# rs41.net
KiCad netlist of a schematic drawn in EAGLE
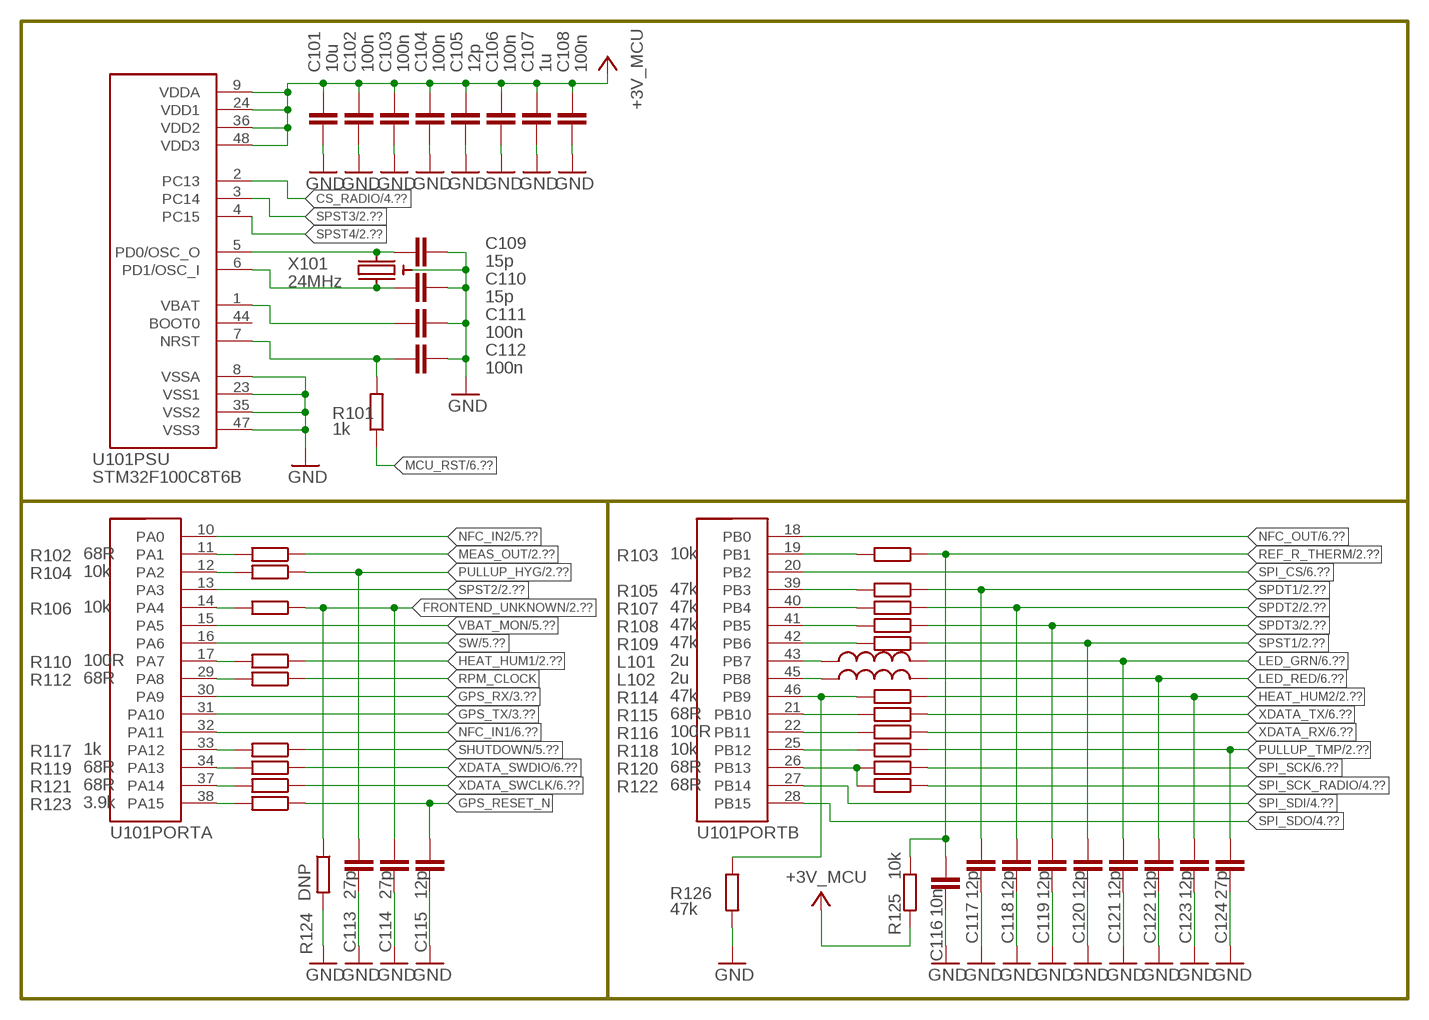
[diagram p0: schematic, sheet 1]
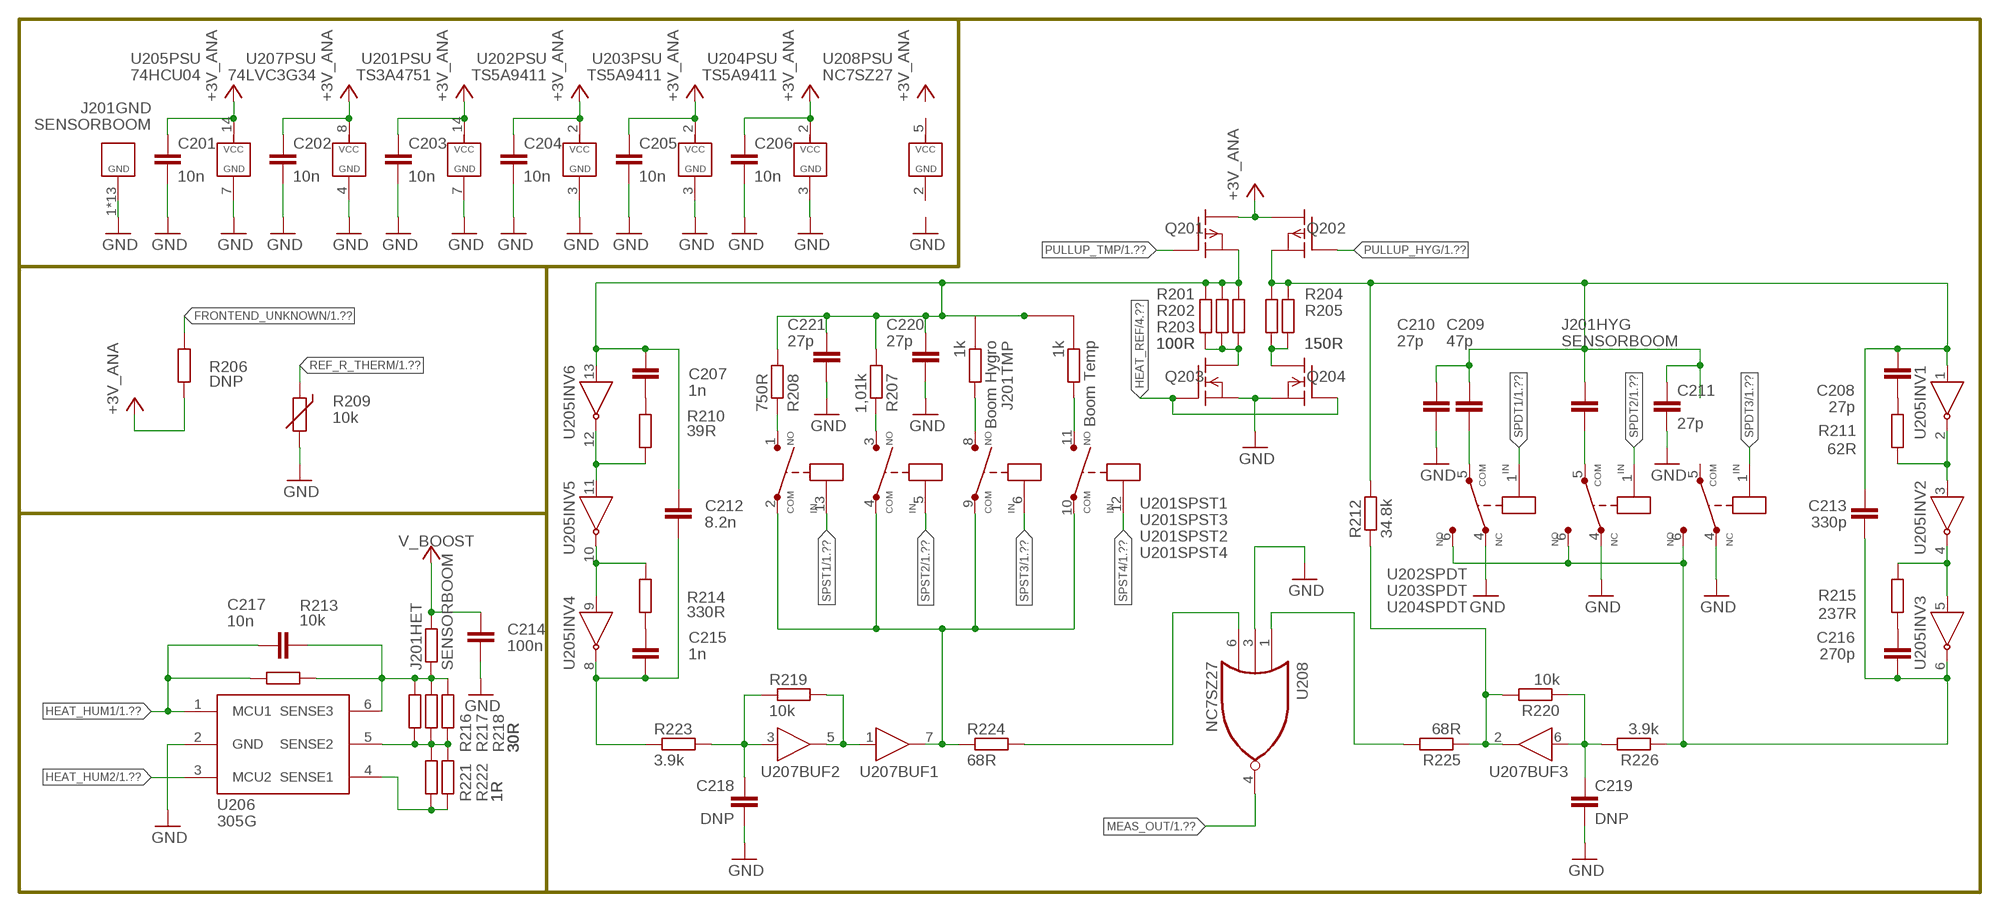
[diagram p1: schematic, sheet 2]
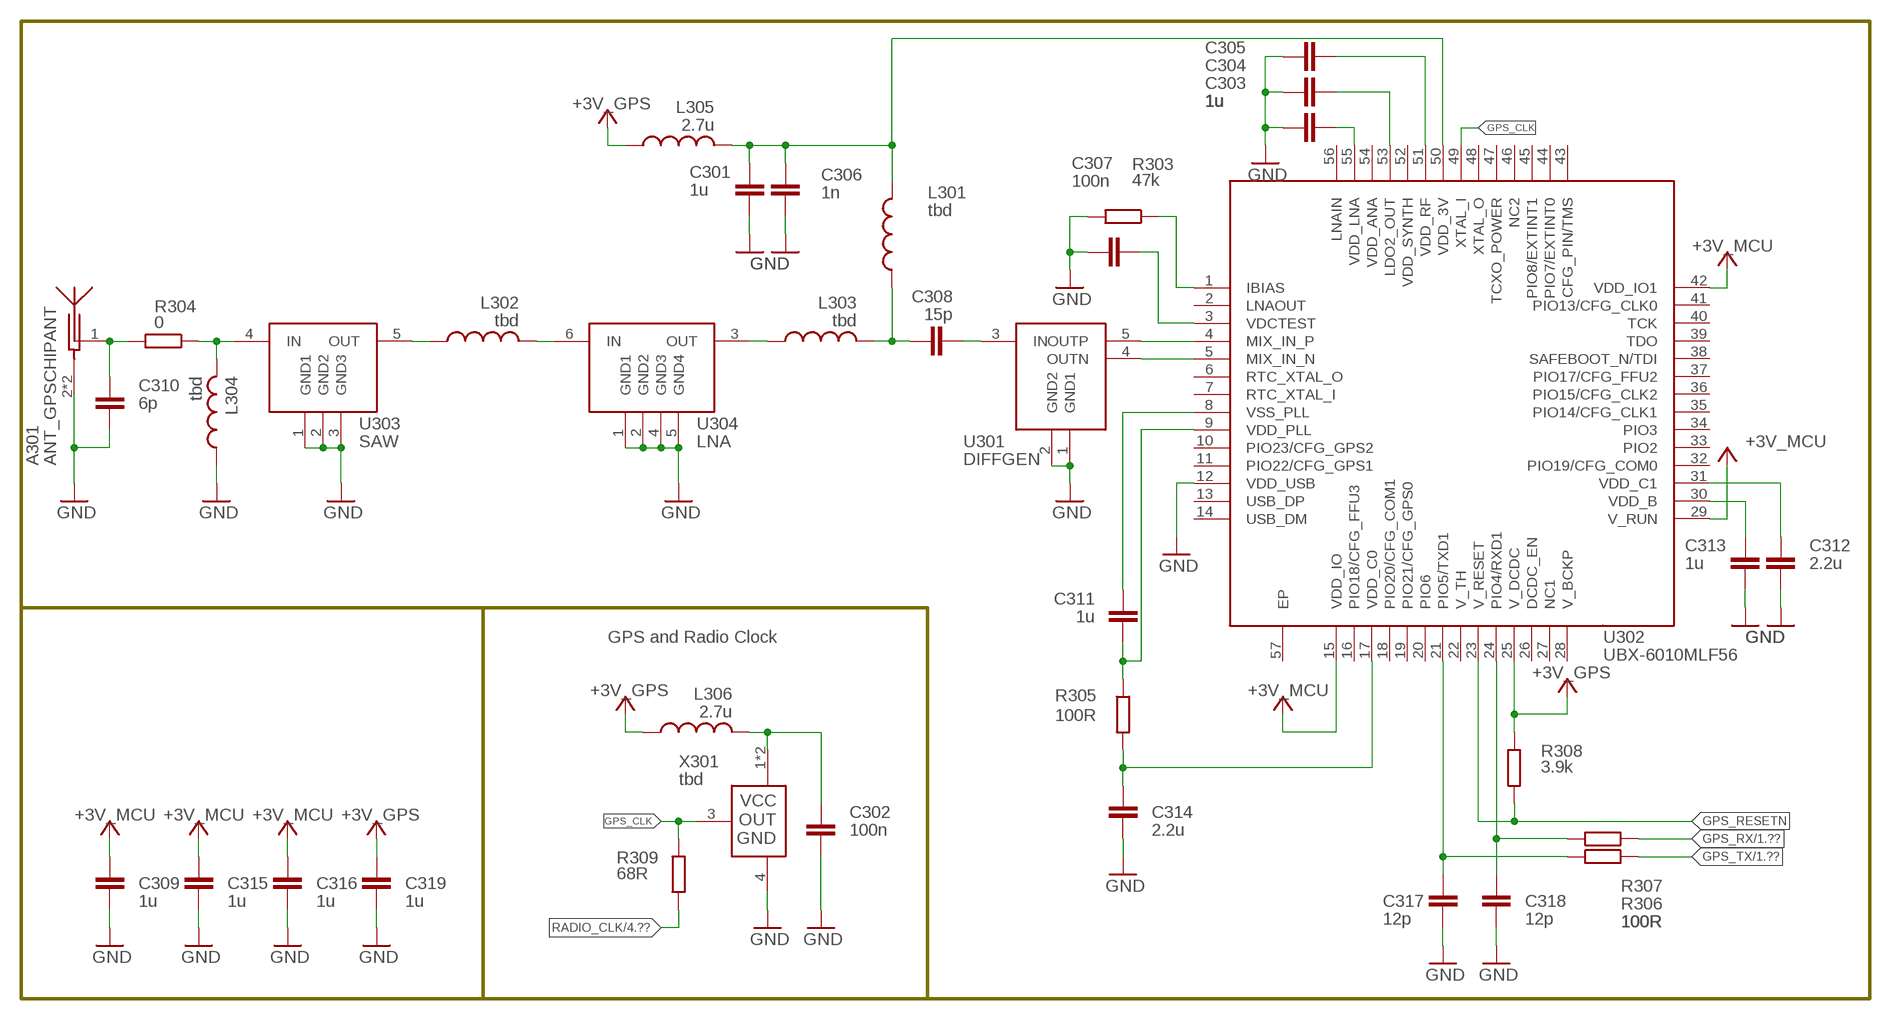
[diagram p2: schematic, sheet 3]
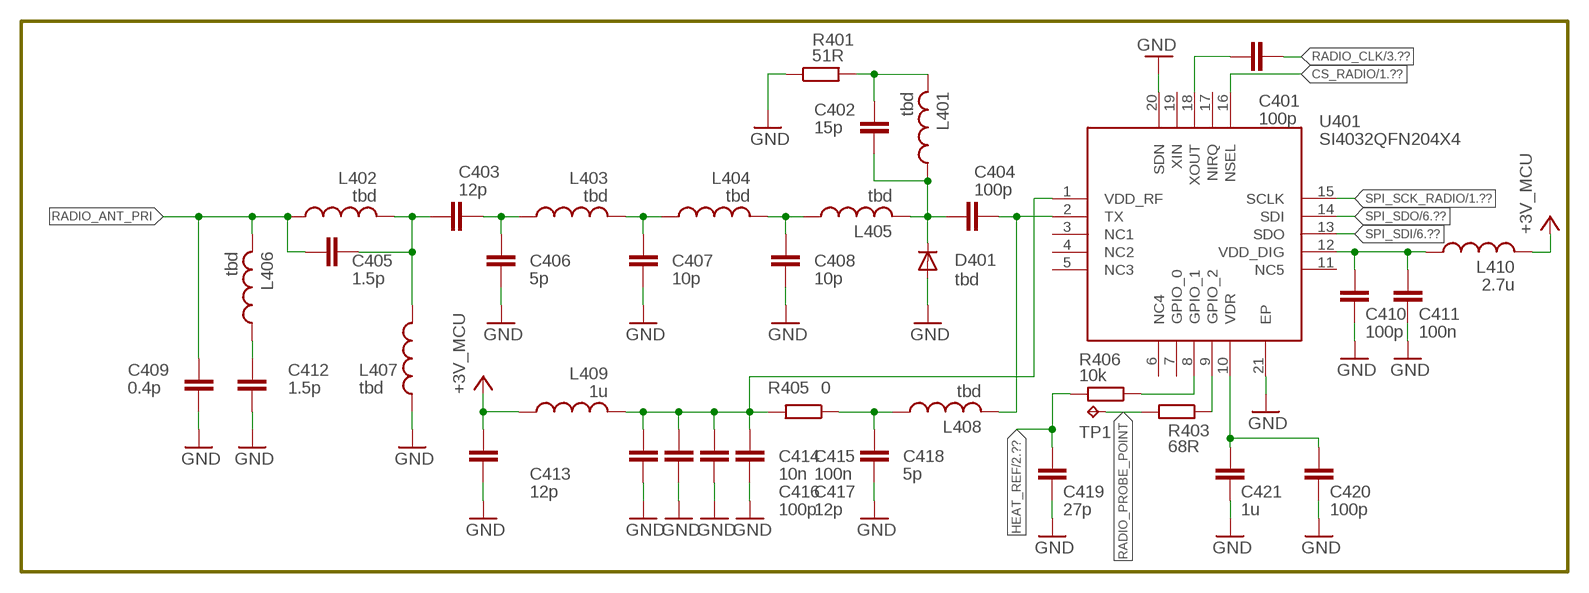
[diagram p3: schematic, sheet 4]
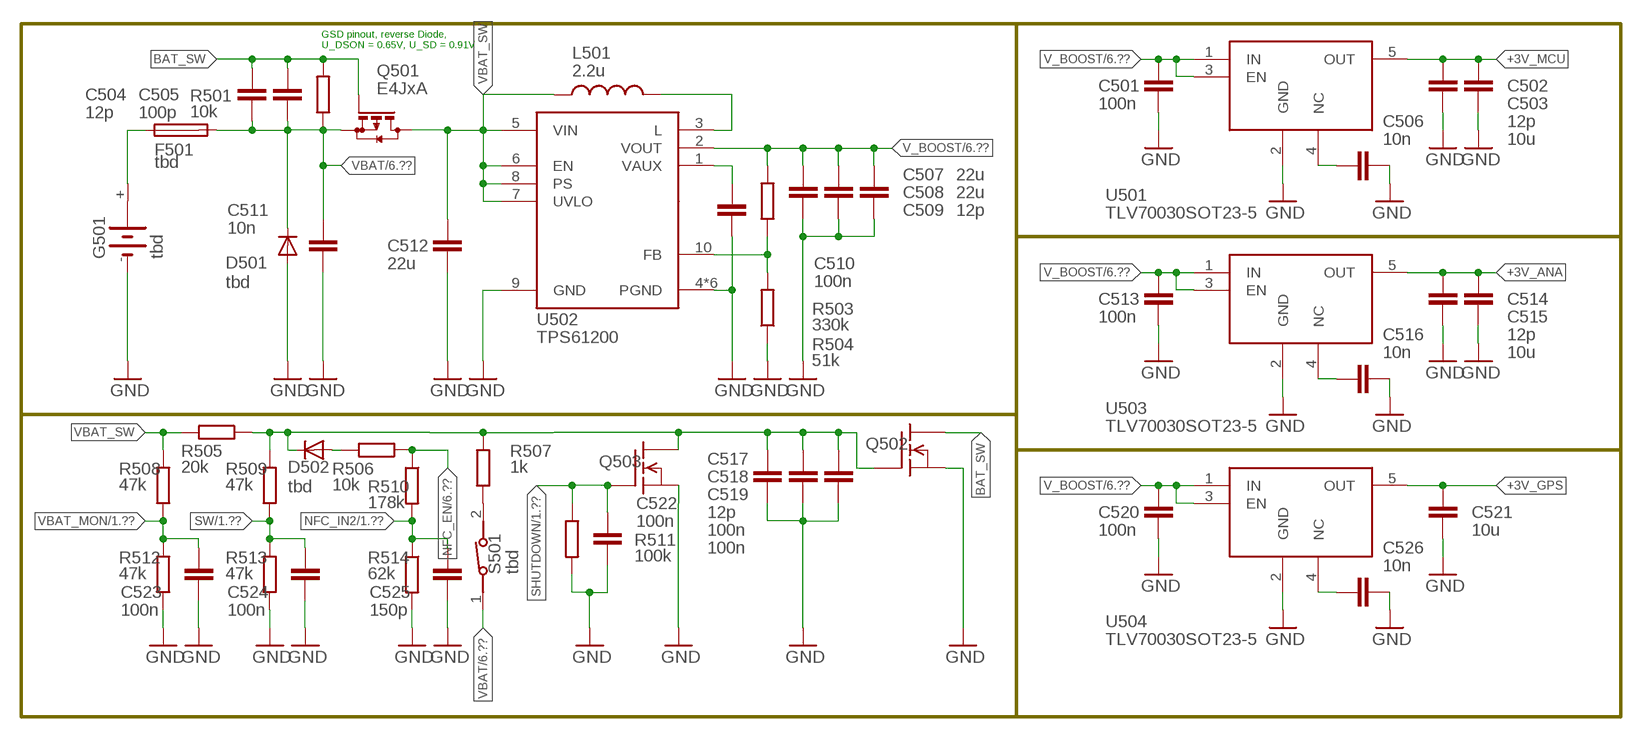
[diagram p4: schematic, sheet 5]
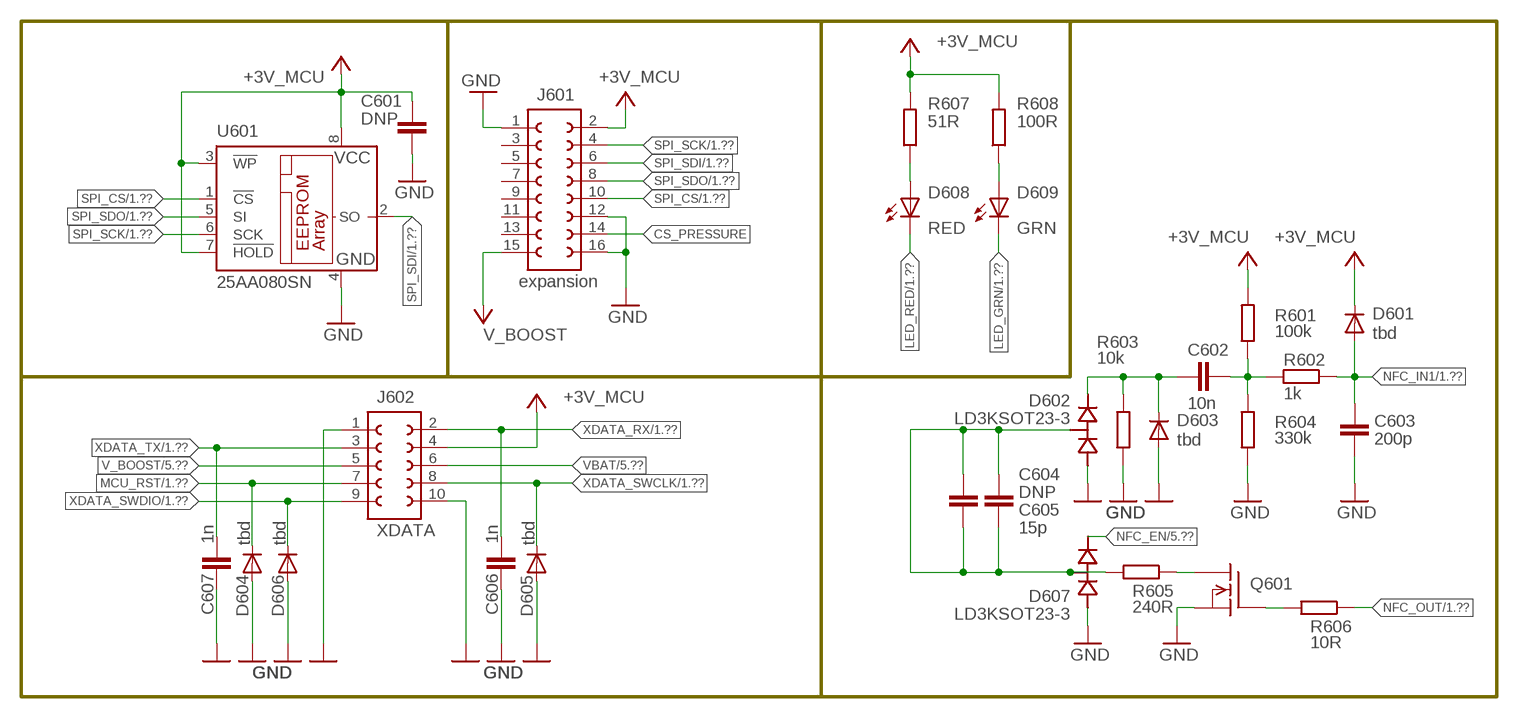
[diagram p5: schematic, sheet 6]

(export (version "E")
  (design (tool "Eeschema 10.0.6"))
  (components
    (comp (ref "C401")
      (value "100p")
      (footprint "eagle-import:C0402")
      (libsource (lib "eagle-import") (part "C-EUC0402"))
    )
    (comp (ref "C402")
      (value "15p")
      (footprint "eagle-import:C0402")
      (libsource (lib "eagle-import") (part "C-EUC0402"))
    )
    (comp (ref "C403")
      (value "12p")
      (footprint "eagle-import:C0402")
      (libsource (lib "eagle-import") (part "C-EUC0402"))
    )
    (comp (ref "C404")
      (value "100p")
      (footprint "eagle-import:C0402")
      (libsource (lib "eagle-import") (part "C-EUC0402"))
    )
    (comp (ref "C405")
      (value "1.5p")
      (footprint "eagle-import:C0402")
      (libsource (lib "eagle-import") (part "C-EUC0402"))
    )
    (comp (ref "C406")
      (value "5p")
      (footprint "eagle-import:C0402")
      (libsource (lib "eagle-import") (part "C-EUC0402"))
    )
    (comp (ref "C407")
      (value "10p")
      (footprint "eagle-import:C0402")
      (libsource (lib "eagle-import") (part "C-EUC0402"))
    )
    (comp (ref "C408")
      (value "10p")
      (footprint "eagle-import:C0402")
      (libsource (lib "eagle-import") (part "C-EUC0402"))
    )
    (comp (ref "C409")
      (value "0.4p")
      (footprint "eagle-import:C0402")
      (libsource (lib "eagle-import") (part "C-EUC0402"))
    )
    (comp (ref "C410")
      (value "100p")
      (footprint "eagle-import:C0402")
      (libsource (lib "eagle-import") (part "C-EUC0402"))
    )
    (comp (ref "C411")
      (value "100n")
      (footprint "eagle-import:C0402")
      (libsource (lib "eagle-import") (part "C-EUC0402"))
    )
    (comp (ref "C412")
      (value "1.5p")
      (footprint "eagle-import:C0402")
      (libsource (lib "eagle-import") (part "C-EUC0402"))
    )
    (comp (ref "C413")
      (value "12p")
      (footprint "eagle-import:C0402")
      (libsource (lib "eagle-import") (part "C-EUC0402"))
    )
    (comp (ref "C414")
      (value "10n")
      (footprint "eagle-import:C0603")
      (libsource (lib "eagle-import") (part "C-EUC0603"))
    )
    (comp (ref "C415")
      (value "100n")
      (footprint "eagle-import:C0402")
      (libsource (lib "eagle-import") (part "C-EUC0402"))
    )
    (comp (ref "C416")
      (value "100p")
      (footprint "eagle-import:C0402")
      (libsource (lib "eagle-import") (part "C-EUC0402"))
    )
    (comp (ref "C417")
      (value "12p")
      (footprint "eagle-import:C0402")
      (libsource (lib "eagle-import") (part "C-EUC0402"))
    )
    (comp (ref "C418")
      (value "5p")
      (footprint "eagle-import:C0402")
      (libsource (lib "eagle-import") (part "C-EUC0402"))
    )
    (comp (ref "C419")
      (value "27p")
      (footprint "eagle-import:C0402")
      (libsource (lib "eagle-import") (part "C-EUC0402"))
    )
    (comp (ref "C420")
      (value "100p")
      (footprint "eagle-import:C0402")
      (libsource (lib "eagle-import") (part "C-EUC0402"))
    )
    (comp (ref "C421")
      (value "1u")
      (footprint "eagle-import:C0402")
      (libsource (lib "eagle-import") (part "C-EUC0402"))
    )
    (comp (ref "D401")
      (value "tbd")
      (footprint "eagle-import:DO41-10")
      (libsource (lib "eagle-import") (part "1N4004"))
    )
    (comp (ref "L401")
      (value "tbd")
      (footprint "eagle-import:0402")
      (libsource (lib "eagle-import") (part "L0402"))
    )
    (comp (ref "L402")
      (value "tbd")
      (footprint "eagle-import:0402")
      (libsource (lib "eagle-import") (part "L0402"))
    )
    (comp (ref "L403")
      (value "tbd")
      (footprint "eagle-import:0402")
      (libsource (lib "eagle-import") (part "L0402"))
    )
    (comp (ref "L404")
      (value "tbd")
      (footprint "eagle-import:0402")
      (libsource (lib "eagle-import") (part "L0402"))
    )
    (comp (ref "L405")
      (value "tbd")
      (footprint "eagle-import:0402")
      (libsource (lib "eagle-import") (part "L0402"))
    )
    (comp (ref "L406")
      (value "tbd")
      (footprint "eagle-import:0402")
      (libsource (lib "eagle-import") (part "L0402"))
    )
    (comp (ref "L407")
      (value "tbd")
      (footprint "eagle-import:0402")
      (libsource (lib "eagle-import") (part "L0402"))
    )
    (comp (ref "L408")
      (value "tbd")
      (footprint "eagle-import:0402")
      (libsource (lib "eagle-import") (part "L0402"))
    )
    (comp (ref "L409")
      (value "1u")
      (footprint "eagle-import:0402")
      (libsource (lib "eagle-import") (part "L0402"))
    )
    (comp (ref "L410")
      (value "2.7u")
      (footprint "eagle-import:0402")
      (libsource (lib "eagle-import") (part "L0402"))
    )
    (comp (ref "R401")
      (value "51R")
      (footprint "eagle-import:R0402")
      (libsource (lib "eagle-import") (part "R-EU_R0402"))
    )
    (comp (ref "R403")
      (value "68R")
      (footprint "eagle-import:R0402")
      (libsource (lib "eagle-import") (part "R-EU_R0402"))
    )
    (comp (ref "R405")
      (value "0")
      (footprint "eagle-import:R0402")
      (libsource (lib "eagle-import") (part "R-EU_R0402"))
    )
    (comp (ref "R406")
      (value "10k")
      (footprint "eagle-import:R0402")
      (libsource (lib "eagle-import") (part "R-EU_R0402"))
    )
    (comp (ref "TP1")
      (value "TPPAD1-13")
      (footprint "eagle-import:P1-13")
      (libsource (lib "eagle-import") (part "TPPAD1-13"))
    )
    (comp (ref "U401")
      (value "SI4032QFN204X4")
      (footprint "eagle-import:QFN20_0.5MM")
      (libsource (lib "eagle-import") (part "SI4032QFN204X4"))
    )
    (comp (ref "C101")
      (value "10u")
      (footprint "eagle-import:C0603")
      (libsource (lib "eagle-import") (part "C-EUC0603"))
    )
    (comp (ref "C102")
      (value "100n")
      (footprint "eagle-import:C0402")
      (libsource (lib "eagle-import") (part "C-EUC0402"))
    )
    (comp (ref "C103")
      (value "100n")
      (footprint "eagle-import:C0402")
      (libsource (lib "eagle-import") (part "C-EUC0402"))
    )
    (comp (ref "C104")
      (value "100n")
      (footprint "eagle-import:C0402")
      (libsource (lib "eagle-import") (part "C-EUC0402"))
    )
    (comp (ref "C105")
      (value "12p")
      (footprint "eagle-import:C0402")
      (libsource (lib "eagle-import") (part "C-EUC0402"))
    )
    (comp (ref "C106")
      (value "100n")
      (footprint "eagle-import:C0402")
      (libsource (lib "eagle-import") (part "C-EUC0402"))
    )
    (comp (ref "C107")
      (value "1u")
      (footprint "eagle-import:C0402")
      (libsource (lib "eagle-import") (part "C-EUC0402"))
    )
    (comp (ref "C108")
      (value "100n")
      (footprint "eagle-import:C0402")
      (libsource (lib "eagle-import") (part "C-EUC0402"))
    )
    (comp (ref "C109")
      (value "15p")
      (footprint "eagle-import:C0402")
      (libsource (lib "eagle-import") (part "C-EUC0402"))
    )
    (comp (ref "C110")
      (value "15p")
      (footprint "eagle-import:C0402")
      (libsource (lib "eagle-import") (part "C-EUC0402"))
    )
    (comp (ref "C111")
      (value "100n")
      (footprint "eagle-import:C0402")
      (libsource (lib "eagle-import") (part "C-EUC0402"))
    )
    (comp (ref "C112")
      (value "100n")
      (footprint "eagle-import:C0402")
      (libsource (lib "eagle-import") (part "C-EUC0402"))
    )
    (comp (ref "C113")
      (value "27p")
      (footprint "eagle-import:C0402")
      (libsource (lib "eagle-import") (part "C-EUC0402"))
    )
    (comp (ref "C114")
      (value "27p")
      (footprint "eagle-import:C0402")
      (libsource (lib "eagle-import") (part "C-EUC0402"))
    )
    (comp (ref "C115")
      (value "12p")
      (footprint "eagle-import:C0402")
      (libsource (lib "eagle-import") (part "C-EUC0402"))
    )
    (comp (ref "C116")
      (value "10n")
      (footprint "eagle-import:C0402")
      (libsource (lib "eagle-import") (part "C-EUC0402"))
    )
    (comp (ref "C117")
      (value "12p")
      (footprint "eagle-import:C0402")
      (libsource (lib "eagle-import") (part "C-EUC0402"))
    )
    (comp (ref "C118")
      (value "12p")
      (footprint "eagle-import:C0402")
      (libsource (lib "eagle-import") (part "C-EUC0402"))
    )
    (comp (ref "C119")
      (value "12p")
      (footprint "eagle-import:C0402")
      (libsource (lib "eagle-import") (part "C-EUC0402"))
    )
    (comp (ref "C120")
      (value "12p")
      (footprint "eagle-import:C0402")
      (libsource (lib "eagle-import") (part "C-EUC0402"))
    )
    (comp (ref "C121")
      (value "12p")
      (footprint "eagle-import:C0402")
      (libsource (lib "eagle-import") (part "C-EUC0402"))
    )
    (comp (ref "C122")
      (value "12p")
      (footprint "eagle-import:C0402")
      (libsource (lib "eagle-import") (part "C-EUC0402"))
    )
    (comp (ref "C123")
      (value "12p")
      (footprint "eagle-import:C0402")
      (libsource (lib "eagle-import") (part "C-EUC0402"))
    )
    (comp (ref "C124")
      (value "27p")
      (footprint "eagle-import:C0402")
      (libsource (lib "eagle-import") (part "C-EUC0402"))
    )
    (comp (ref "L101")
      (value "2u")
      (footprint "eagle-import:0402")
      (libsource (lib "eagle-import") (part "L0402"))
    )
    (comp (ref "L102")
      (value "2u")
      (footprint "eagle-import:0402")
      (libsource (lib "eagle-import") (part "L0402"))
    )
    (comp (ref "R101")
      (value "1k")
      (footprint "eagle-import:R0402")
      (libsource (lib "eagle-import") (part "R-EU_R0402"))
    )
    (comp (ref "R102")
      (value "68R")
      (footprint "eagle-import:R0402")
      (libsource (lib "eagle-import") (part "R-EU_R0402"))
    )
    (comp (ref "R103")
      (value "10k")
      (footprint "eagle-import:R0402")
      (libsource (lib "eagle-import") (part "R-EU_R0402"))
    )
    (comp (ref "R104")
      (value "10k")
      (footprint "eagle-import:R0402")
      (libsource (lib "eagle-import") (part "R-EU_R0402"))
    )
    (comp (ref "R105")
      (value "47k")
      (footprint "eagle-import:R0402")
      (libsource (lib "eagle-import") (part "R-EU_R0402"))
    )
    (comp (ref "R106")
      (value "10k")
      (footprint "eagle-import:R0402")
      (libsource (lib "eagle-import") (part "R-EU_R0402"))
    )
    (comp (ref "R107")
      (value "47k")
      (footprint "eagle-import:R0402")
      (libsource (lib "eagle-import") (part "R-EU_R0402"))
    )
    (comp (ref "R108")
      (value "47k")
      (footprint "eagle-import:R0402")
      (libsource (lib "eagle-import") (part "R-EU_R0402"))
    )
    (comp (ref "R109")
      (value "47k")
      (footprint "eagle-import:R0402")
      (libsource (lib "eagle-import") (part "R-EU_R0402"))
    )
    (comp (ref "R110")
      (value "100R")
      (footprint "eagle-import:R0402")
      (libsource (lib "eagle-import") (part "R-EU_R0402"))
    )
    (comp (ref "R112")
      (value "68R")
      (footprint "eagle-import:R0402")
      (libsource (lib "eagle-import") (part "R-EU_R0402"))
    )
    (comp (ref "R114")
      (value "47k")
      (footprint "eagle-import:R0402")
      (libsource (lib "eagle-import") (part "R-EU_R0402"))
    )
    (comp (ref "R115")
      (value "68R")
      (footprint "eagle-import:R0402")
      (libsource (lib "eagle-import") (part "R-EU_R0402"))
    )
    (comp (ref "R116")
      (value "100R")
      (footprint "eagle-import:R0402")
      (libsource (lib "eagle-import") (part "R-EU_R0402"))
    )
    (comp (ref "R117")
      (value "1k")
      (footprint "eagle-import:R0402")
      (libsource (lib "eagle-import") (part "R-EU_R0402"))
    )
    (comp (ref "R118")
      (value "10k")
      (footprint "eagle-import:R0402")
      (libsource (lib "eagle-import") (part "R-EU_R0402"))
    )
    (comp (ref "R119")
      (value "68R")
      (footprint "eagle-import:R0402")
      (libsource (lib "eagle-import") (part "R-EU_R0402"))
    )
    (comp (ref "R120")
      (value "68R")
      (footprint "eagle-import:R0402")
      (libsource (lib "eagle-import") (part "R-EU_R0402"))
    )
    (comp (ref "R121")
      (value "68R")
      (footprint "eagle-import:R0402")
      (libsource (lib "eagle-import") (part "R-EU_R0402"))
    )
    (comp (ref "R122")
      (value "68R")
      (footprint "eagle-import:R0402")
      (libsource (lib "eagle-import") (part "R-EU_R0402"))
    )
    (comp (ref "R123")
      (value "3.9k")
      (footprint "eagle-import:R0402")
      (libsource (lib "eagle-import") (part "R-EU_R0402"))
    )
    (comp (ref "R124")
      (value "DNP")
      (footprint "eagle-import:R0402")
      (libsource (lib "eagle-import") (part "R-EU_R0402"))
    )
    (comp (ref "R125")
      (value "10k")
      (footprint "eagle-import:R0402")
      (libsource (lib "eagle-import") (part "R-EU_R0402"))
    )
    (comp (ref "R126")
      (value "47k")
      (footprint "eagle-import:R0402")
      (libsource (lib "eagle-import") (part "R-EU_R0402"))
    )
    (comp (ref "U101")
      (value "STM32F100C8T6B")
      (footprint "eagle-import:LQFP48")
      (libsource (lib "eagle-import") (part "STM32F100C8LQFP48"))
    )
    (comp (ref "X101")
      (value "24MHz")
      (footprint "eagle-import:OSCCC650X400X120")
      (libsource (lib "eagle-import") (part "OSC_MCU"))
    )
    (comp (ref "A301")
      (value "ANT_GPSCHIPANT")
      (footprint "eagle-import:DFN100X60X40-3")
      (libsource (lib "eagle-import") (part "ANT_GPSCHIPANT"))
    )
    (comp (ref "C301")
      (value "1u")
      (footprint "eagle-import:C0402")
      (libsource (lib "eagle-import") (part "C-EUC0402"))
    )
    (comp (ref "C302")
      (value "100n")
      (footprint "eagle-import:C0402")
      (libsource (lib "eagle-import") (part "C-EUC0402"))
    )
    (comp (ref "C303")
      (value "1u")
      (footprint "eagle-import:C0402")
      (libsource (lib "eagle-import") (part "C-EUC0402"))
    )
    (comp (ref "C304")
      (value "1u")
      (footprint "eagle-import:C0402")
      (libsource (lib "eagle-import") (part "C-EUC0402"))
    )
    (comp (ref "C305")
      (value "1u")
      (footprint "eagle-import:C0402")
      (libsource (lib "eagle-import") (part "C-EUC0402"))
    )
    (comp (ref "C306")
      (value "1n")
      (footprint "eagle-import:C0402")
      (libsource (lib "eagle-import") (part "C-EUC0402"))
    )
    (comp (ref "C307")
      (value "100n")
      (footprint "eagle-import:C0402")
      (libsource (lib "eagle-import") (part "C-EUC0402"))
    )
    (comp (ref "C308")
      (value "15p")
      (footprint "eagle-import:C0402")
      (libsource (lib "eagle-import") (part "C-EUC0402"))
    )
    (comp (ref "C309")
      (value "1u")
      (footprint "eagle-import:C0402")
      (libsource (lib "eagle-import") (part "C-EUC0402"))
    )
    (comp (ref "C310")
      (value "6p")
      (footprint "eagle-import:C0402")
      (libsource (lib "eagle-import") (part "C-EUC0402"))
    )
    (comp (ref "C311")
      (value "1u")
      (footprint "eagle-import:C0402")
      (libsource (lib "eagle-import") (part "C-EUC0402"))
    )
    (comp (ref "C312")
      (value "2.2u")
      (footprint "eagle-import:C0603")
      (libsource (lib "eagle-import") (part "C-EUC0603"))
    )
    (comp (ref "C313")
      (value "1u")
      (footprint "eagle-import:C0402")
      (libsource (lib "eagle-import") (part "C-EUC0402"))
    )
    (comp (ref "C314")
      (value "2.2u")
      (footprint "eagle-import:C0603")
      (libsource (lib "eagle-import") (part "C-EUC0603"))
    )
    (comp (ref "C315")
      (value "1u")
      (footprint "eagle-import:C0402")
      (libsource (lib "eagle-import") (part "C-EUC0402"))
    )
    (comp (ref "C316")
      (value "1u")
      (footprint "eagle-import:C0402")
      (libsource (lib "eagle-import") (part "C-EUC0402"))
    )
    (comp (ref "C317")
      (value "12p")
      (footprint "eagle-import:C0402")
      (libsource (lib "eagle-import") (part "C-EUC0402"))
    )
    (comp (ref "C318")
      (value "12p")
      (footprint "eagle-import:C0402")
      (libsource (lib "eagle-import") (part "C-EUC0402"))
    )
    (comp (ref "C319")
      (value "1u")
      (footprint "eagle-import:C0402")
      (libsource (lib "eagle-import") (part "C-EUC0402"))
    )
    (comp (ref "L301")
      (value "tbd")
      (footprint "eagle-import:0402")
      (libsource (lib "eagle-import") (part "L0402"))
    )
    (comp (ref "L302")
      (value "tbd")
      (footprint "eagle-import:0402")
      (libsource (lib "eagle-import") (part "L0402"))
    )
    (comp (ref "L303")
      (value "tbd")
      (footprint "eagle-import:0402")
      (libsource (lib "eagle-import") (part "L0402"))
    )
    (comp (ref "L304")
      (value "tbd")
      (footprint "eagle-import:0402")
      (libsource (lib "eagle-import") (part "L0402"))
    )
    (comp (ref "L305")
      (value "2.7u")
      (footprint "eagle-import:0402")
      (libsource (lib "eagle-import") (part "L0402"))
    )
    (comp (ref "L306")
      (value "2.7u")
      (footprint "eagle-import:0402")
      (libsource (lib "eagle-import") (part "L0402"))
    )
    (comp (ref "R303")
      (value "47k")
      (footprint "eagle-import:R0402")
      (libsource (lib "eagle-import") (part "R-EU_R0402"))
    )
    (comp (ref "R304")
      (value "0")
      (footprint "eagle-import:R0402")
      (libsource (lib "eagle-import") (part "R-EU_R0402"))
    )
    (comp (ref "R305")
      (value "100R")
      (footprint "eagle-import:R0402")
      (libsource (lib "eagle-import") (part "R-EU_R0402"))
    )
    (comp (ref "R306")
      (value "100R")
      (footprint "eagle-import:R0402")
      (libsource (lib "eagle-import") (part "R-EU_R0402"))
    )
    (comp (ref "R307")
      (value "100R")
      (footprint "eagle-import:R0402")
      (libsource (lib "eagle-import") (part "R-EU_R0402"))
    )
    (comp (ref "R308")
      (value "3.9k")
      (footprint "eagle-import:R0402")
      (libsource (lib "eagle-import") (part "R-EU_R0402"))
    )
    (comp (ref "R309")
      (value "68R")
      (footprint "eagle-import:R0402")
      (libsource (lib "eagle-import") (part "R-EU_R0402"))
    )
    (comp (ref "U301")
      (value "DIFFGEN")
      (footprint "eagle-import:SOT23-5")
      (libsource (lib "eagle-import") (part "DIFFGEN"))
    )
    (comp (ref "U302")
      (value "UBX-6010MLF56")
      (footprint "eagle-import:QFN56_0.5MM")
      (libsource (lib "eagle-import") (part "UBX-6010MLF56"))
    )
    (comp (ref "U303")
      (value "SAW")
      (footprint "eagle-import:SOT23-5")
      (libsource (lib "eagle-import") (part "SAW"))
    )
    (comp (ref "U304")
      (value "LNA")
      (footprint "eagle-import:SOT23-6")
      (libsource (lib "eagle-import") (part "LNA"))
    )
    (comp (ref "X301")
      (value "tbd")
      (footprint "eagle-import:OSCCC650X400X120")
      (libsource (lib "eagle-import") (part "OSC_GPSXTAL4"))
    )
    (comp (ref "C201")
      (value "10n")
      (footprint "eagle-import:C0402")
      (libsource (lib "eagle-import") (part "C-EUC0402"))
    )
    (comp (ref "C202")
      (value "10n")
      (footprint "eagle-import:C0402")
      (libsource (lib "eagle-import") (part "C-EUC0402"))
    )
    (comp (ref "C203")
      (value "10n")
      (footprint "eagle-import:C0402")
      (libsource (lib "eagle-import") (part "C-EUC0402"))
    )
    (comp (ref "C204")
      (value "10n")
      (footprint "eagle-import:C0402")
      (libsource (lib "eagle-import") (part "C-EUC0402"))
    )
    (comp (ref "C205")
      (value "10n")
      (footprint "eagle-import:C0402")
      (libsource (lib "eagle-import") (part "C-EUC0402"))
    )
    (comp (ref "C206")
      (value "10n")
      (footprint "eagle-import:C0402")
      (libsource (lib "eagle-import") (part "C-EUC0402"))
    )
    (comp (ref "C207")
      (value "1n")
      (footprint "eagle-import:C0402")
      (libsource (lib "eagle-import") (part "C-EUC0402"))
    )
    (comp (ref "C208")
      (value "27p")
      (footprint "eagle-import:C0402")
      (libsource (lib "eagle-import") (part "C-EUC0402"))
    )
    (comp (ref "C209")
      (value "47p")
      (footprint "eagle-import:C0603")
      (libsource (lib "eagle-import") (part "C-EUC0603"))
    )
    (comp (ref "C210")
      (value "27p")
      (footprint "eagle-import:C0402")
      (libsource (lib "eagle-import") (part "C-EUC0402"))
    )
    (comp (ref "C211")
      (value "27p")
      (footprint "eagle-import:C0402")
      (libsource (lib "eagle-import") (part "C-EUC0402"))
    )
    (comp (ref "C212")
      (value "8.2n")
      (footprint "eagle-import:C0603")
      (libsource (lib "eagle-import") (part "C-EUC0603"))
    )
    (comp (ref "C213")
      (value "330p")
      (footprint "eagle-import:C0402")
      (libsource (lib "eagle-import") (part "C-EUC0402"))
    )
    (comp (ref "C214")
      (value "100n")
      (footprint "eagle-import:C0402")
      (libsource (lib "eagle-import") (part "C-EUC0402"))
    )
    (comp (ref "C215")
      (value "1n")
      (footprint "eagle-import:C0402")
      (libsource (lib "eagle-import") (part "C-EUC0402"))
    )
    (comp (ref "C216")
      (value "270p")
      (footprint "eagle-import:C0402")
      (libsource (lib "eagle-import") (part "C-EUC0402"))
    )
    (comp (ref "C217")
      (value "10n")
      (footprint "eagle-import:C0402")
      (libsource (lib "eagle-import") (part "C-EUC0402"))
    )
    (comp (ref "C218")
      (value "DNP")
      (footprint "eagle-import:C0402")
      (libsource (lib "eagle-import") (part "C-EUC0402"))
    )
    (comp (ref "C219")
      (value "DNP")
      (footprint "eagle-import:C0402")
      (libsource (lib "eagle-import") (part "C-EUC0402"))
    )
    (comp (ref "C220")
      (value "27p")
      (footprint "eagle-import:C0402")
      (libsource (lib "eagle-import") (part "C-EUC0402"))
    )
    (comp (ref "C221")
      (value "27p")
      (footprint "eagle-import:C0402")
      (libsource (lib "eagle-import") (part "C-EUC0402"))
    )
    (comp (ref "J201")
      (value "SENSORBOOM")
      (footprint "eagle-import:687316124422")
      (libsource (lib "eagle-import") (part "SENSORBOOM"))
    )
    (comp (ref "Q201")
      (value "BSS92")
      (footprint "eagle-import:TO92")
      (libsource (lib "eagle-import") (part "BSS92"))
    )
    (comp (ref "Q202")
      (value "BSS92")
      (footprint "eagle-import:TO92")
      (libsource (lib "eagle-import") (part "BSS92"))
    )
    (comp (ref "Q203")
      (value "BSS101")
      (footprint "eagle-import:TO92")
      (libsource (lib "eagle-import") (part "BSS101"))
    )
    (comp (ref "Q204")
      (value "BSS101")
      (footprint "eagle-import:TO92")
      (libsource (lib "eagle-import") (part "BSS101"))
    )
    (comp (ref "R201")
      (value "100R")
      (footprint "eagle-import:R0603")
      (libsource (lib "eagle-import") (part "R-EU_R0603"))
    )
    (comp (ref "R202")
      (value "100R")
      (footprint "eagle-import:R0603")
      (libsource (lib "eagle-import") (part "R-EU_R0603"))
    )
    (comp (ref "R203")
      (value "100R")
      (footprint "eagle-import:R0603")
      (libsource (lib "eagle-import") (part "R-EU_R0603"))
    )
    (comp (ref "R204")
      (value "150R")
      (footprint "eagle-import:R0603")
      (libsource (lib "eagle-import") (part "R-EU_R0603"))
    )
    (comp (ref "R205")
      (value "150R")
      (footprint "eagle-import:R0603")
      (libsource (lib "eagle-import") (part "R-EU_R0603"))
    )
    (comp (ref "R206")
      (value "DNP")
      (footprint "eagle-import:R0402")
      (libsource (lib "eagle-import") (part "R-EU_R0402"))
    )
    (comp (ref "R207")
      (value "1,01k")
      (footprint "eagle-import:R0805")
      (libsource (lib "eagle-import") (part "R-EU_R0805"))
    )
    (comp (ref "R208")
      (value "750R")
      (footprint "eagle-import:R0805")
      (libsource (lib "eagle-import") (part "R-EU_R0805"))
    )
    (comp (ref "R209")
      (value "10k")
      (footprint "eagle-import:0402")
      (libsource (lib "eagle-import") (part "THERMISTOR0402"))
    )
    (comp (ref "R210")
      (value "39R")
      (footprint "eagle-import:R0402")
      (libsource (lib "eagle-import") (part "R-EU_R0402"))
    )
    (comp (ref "R211")
      (value "62R")
      (footprint "eagle-import:R0402")
      (libsource (lib "eagle-import") (part "R-EU_R0402"))
    )
    (comp (ref "R212")
      (value "34.8k")
      (footprint "eagle-import:R0402")
      (libsource (lib "eagle-import") (part "R-EU_R0402"))
    )
    (comp (ref "R213")
      (value "10k")
      (footprint "eagle-import:R0402")
      (libsource (lib "eagle-import") (part "R-EU_R0402"))
    )
    (comp (ref "R214")
      (value "330R")
      (footprint "eagle-import:R0402")
      (libsource (lib "eagle-import") (part "R-EU_R0402"))
    )
    (comp (ref "R215")
      (value "237R")
      (footprint "eagle-import:R0402")
      (libsource (lib "eagle-import") (part "R-EU_R0402"))
    )
    (comp (ref "R216")
      (value "30R")
      (footprint "eagle-import:R0603")
      (libsource (lib "eagle-import") (part "R-EU_R0603"))
    )
    (comp (ref "R217")
      (value "30R")
      (footprint "eagle-import:R0603")
      (libsource (lib "eagle-import") (part "R-EU_R0603"))
    )
    (comp (ref "R218")
      (value "30R")
      (footprint "eagle-import:R0603")
      (libsource (lib "eagle-import") (part "R-EU_R0603"))
    )
    (comp (ref "R219")
      (value "10k")
      (footprint "eagle-import:R0402")
      (libsource (lib "eagle-import") (part "R-EU_R0402"))
    )
    (comp (ref "R220")
      (value "10k")
      (footprint "eagle-import:R0402")
      (libsource (lib "eagle-import") (part "R-EU_R0402"))
    )
    (comp (ref "R221")
      (value "1R")
      (footprint "eagle-import:R0402")
      (libsource (lib "eagle-import") (part "R-EU_R0402"))
    )
    (comp (ref "R222")
      (value "1R")
      (footprint "eagle-import:R0402")
      (libsource (lib "eagle-import") (part "R-EU_R0402"))
    )
    (comp (ref "R223")
      (value "3.9k")
      (footprint "eagle-import:R0402")
      (libsource (lib "eagle-import") (part "R-EU_R0402"))
    )
    (comp (ref "R224")
      (value "68R")
      (footprint "eagle-import:R0402")
      (libsource (lib "eagle-import") (part "R-EU_R0402"))
    )
    (comp (ref "R225")
      (value "68R")
      (footprint "eagle-import:R0402")
      (libsource (lib "eagle-import") (part "R-EU_R0402"))
    )
    (comp (ref "R226")
      (value "3.9k")
      (footprint "eagle-import:R0402")
      (libsource (lib "eagle-import") (part "R-EU_R0402"))
    )
    (comp (ref "U201")
      (value "TS3A4751")
      (footprint "eagle-import:TSSOP14")
      (libsource (lib "eagle-import") (part "TS3A4751"))
    )
    (comp (ref "U202")
      (value "TS5A9411")
      (footprint "eagle-import:SOT23-6")
      (libsource (lib "eagle-import") (part "TS5A9411"))
    )
    (comp (ref "U203")
      (value "TS5A9411")
      (footprint "eagle-import:SOT23-6")
      (libsource (lib "eagle-import") (part "TS5A9411"))
    )
    (comp (ref "U204")
      (value "TS5A9411")
      (footprint "eagle-import:SOT23-6")
      (libsource (lib "eagle-import") (part "TS5A9411"))
    )
    (comp (ref "U205")
      (value "74HCU04")
      (footprint "eagle-import:TSSOP14")
      (libsource (lib "eagle-import") (part "74HCU04"))
    )
    (comp (ref "U206")
      (value "305G")
      (footprint "eagle-import:SOT23-6")
      (libsource (lib "eagle-import") (part "305G"))
    )
    (comp (ref "U207")
      (value "74LVC3G34")
      (footprint "eagle-import:GHI-IC_VSSOP8(TI)")
      (libsource (lib "eagle-import") (part "74LVC3G34"))
    )
    (comp (ref "U208")
      (value "NC7SZ27")
      (footprint "eagle-import:SOT23-6")
      (libsource (lib "eagle-import") (part "NC7SZ27"))
    )
    (comp (ref "C601")
      (value "DNP")
      (footprint "eagle-import:C0402")
      (libsource (lib "eagle-import") (part "C-EUC0402"))
    )
    (comp (ref "C602")
      (value "10n")
      (footprint "eagle-import:C0402")
      (libsource (lib "eagle-import") (part "C-EUC0402"))
    )
    (comp (ref "C603")
      (value "200p")
      (footprint "eagle-import:C0402")
      (libsource (lib "eagle-import") (part "C-EUC0402"))
    )
    (comp (ref "C604")
      (value "DNP")
      (footprint "eagle-import:C0402")
      (libsource (lib "eagle-import") (part "C-EUC0402"))
    )
    (comp (ref "C605")
      (value "15p")
      (footprint "eagle-import:C0402")
      (libsource (lib "eagle-import") (part "C-EUC0402"))
    )
    (comp (ref "C606")
      (value "1n")
      (footprint "eagle-import:C0402")
      (libsource (lib "eagle-import") (part "C-EUC0402"))
    )
    (comp (ref "C607")
      (value "1n")
      (footprint "eagle-import:C0402")
      (libsource (lib "eagle-import") (part "C-EUC0402"))
    )
    (comp (ref "D601")
      (value "tbd")
      (footprint "eagle-import:DO41-10")
      (libsource (lib "eagle-import") (part "1N4004"))
    )
    (comp (ref "D602")
      (value "LD3KSOT23-3")
      (footprint "eagle-import:SOT23-3")
      (libsource (lib "eagle-import") (part "LD3KSOT23-3"))
    )
    (comp (ref "D603")
      (value "tbd")
      (footprint "eagle-import:DO41-10")
      (libsource (lib "eagle-import") (part "1N4004"))
    )
    (comp (ref "D604")
      (value "tbd")
      (footprint "eagle-import:DO41-10")
      (libsource (lib "eagle-import") (part "1N4004"))
    )
    (comp (ref "D605")
      (value "tbd")
      (footprint "eagle-import:DO41-10")
      (libsource (lib "eagle-import") (part "1N4004"))
    )
    (comp (ref "D606")
      (value "tbd")
      (footprint "eagle-import:DO41-10")
      (libsource (lib "eagle-import") (part "1N4004"))
    )
    (comp (ref "D607")
      (value "LD3KSOT23-3")
      (footprint "eagle-import:SOT23-3")
      (libsource (lib "eagle-import") (part "LD3KSOT23-3"))
    )
    (comp (ref "D608")
      (value "RED")
      (footprint "eagle-import:CHIPLED_0603")
      (libsource (lib "eagle-import") (part "LEDCHIPLED_0603"))
    )
    (comp (ref "D609")
      (value "GRN")
      (footprint "eagle-import:CHIPLED_0603")
      (libsource (lib "eagle-import") (part "LEDCHIPLED_0603"))
    )
    (comp (ref "J601")
      (value "expansion")
      (footprint "eagle-import:62001621121")
      (libsource (lib "eagle-import") (part "62001621121"))
    )
    (comp (ref "J602")
      (value "XDATA")
      (footprint "eagle-import:62001021121")
      (libsource (lib "eagle-import") (part "62001021121"))
    )
    (comp (ref "Q601")
      (value "BSS101")
      (footprint "eagle-import:TO92")
      (libsource (lib "eagle-import") (part "BSS101"))
    )
    (comp (ref "R601")
      (value "100k")
      (footprint "eagle-import:R0402")
      (libsource (lib "eagle-import") (part "R-EU_R0402"))
    )
    (comp (ref "R602")
      (value "1k")
      (footprint "eagle-import:R0402")
      (libsource (lib "eagle-import") (part "R-EU_R0402"))
    )
    (comp (ref "R603")
      (value "10k")
      (footprint "eagle-import:R0402")
      (libsource (lib "eagle-import") (part "R-EU_R0402"))
    )
    (comp (ref "R604")
      (value "330k")
      (footprint "eagle-import:R0402")
      (libsource (lib "eagle-import") (part "R-EU_R0402"))
    )
    (comp (ref "R605")
      (value "240R")
      (footprint "eagle-import:R0402")
      (libsource (lib "eagle-import") (part "R-EU_R0402"))
    )
    (comp (ref "R606")
      (value "10R")
      (footprint "eagle-import:R0402")
      (libsource (lib "eagle-import") (part "R-EU_R0402"))
    )
    (comp (ref "R607")
      (value "51R")
      (footprint "eagle-import:R0402")
      (libsource (lib "eagle-import") (part "R-EU_R0402"))
    )
    (comp (ref "R608")
      (value "100R")
      (footprint "eagle-import:R0402")
      (libsource (lib "eagle-import") (part "R-EU_R0402"))
    )
    (comp (ref "U601")
      (value "25AA080SN")
      (footprint "eagle-import:SO-08")
      (fields (field (name "MF") "MICROCHIP") (field (name "MPN") "25AA080/SN"))
      (libsource (lib "eagle-import") (part "25SNAA080"))
    )
    (comp (ref "C501")
      (value "100n")
      (footprint "eagle-import:C0402")
      (libsource (lib "eagle-import") (part "C-EUC0402"))
    )
    (comp (ref "C502")
      (value "12p")
      (footprint "eagle-import:C0402")
      (libsource (lib "eagle-import") (part "C-EUC0402"))
    )
    (comp (ref "C503")
      (value "10u")
      (footprint "eagle-import:C0603")
      (libsource (lib "eagle-import") (part "C-EUC0603"))
    )
    (comp (ref "C504")
      (value "12p")
      (footprint "eagle-import:C0402")
      (libsource (lib "eagle-import") (part "C-EUC0402"))
    )
    (comp (ref "C505")
      (value "100p")
      (footprint "eagle-import:C0402")
      (libsource (lib "eagle-import") (part "C-EUC0402"))
    )
    (comp (ref "C506")
      (value "10n")
      (footprint "eagle-import:C0402")
      (libsource (lib "eagle-import") (part "C-EUC0402"))
    )
    (comp (ref "C507")
      (value "22u")
      (footprint "eagle-import:C0805")
      (libsource (lib "eagle-import") (part "C-EUC0805"))
    )
    (comp (ref "C508")
      (value "22u")
      (footprint "eagle-import:C0805")
      (libsource (lib "eagle-import") (part "C-EUC0805"))
    )
    (comp (ref "C509")
      (value "12p")
      (footprint "eagle-import:C0402")
      (libsource (lib "eagle-import") (part "C-EUC0402"))
    )
    (comp (ref "C510")
      (value "100n")
      (footprint "eagle-import:C0402")
      (libsource (lib "eagle-import") (part "C-EUC0402"))
    )
    (comp (ref "C511")
      (value "10n")
      (footprint "eagle-import:C0402")
      (libsource (lib "eagle-import") (part "C-EUC0402"))
    )
    (comp (ref "C512")
      (value "22u")
      (footprint "eagle-import:C0805")
      (libsource (lib "eagle-import") (part "C-EUC0805"))
    )
    (comp (ref "C513")
      (value "100n")
      (footprint "eagle-import:C0402")
      (libsource (lib "eagle-import") (part "C-EUC0402"))
    )
    (comp (ref "C514")
      (value "12p")
      (footprint "eagle-import:C0402")
      (libsource (lib "eagle-import") (part "C-EUC0402"))
    )
    (comp (ref "C515")
      (value "10u")
      (footprint "eagle-import:C0603")
      (libsource (lib "eagle-import") (part "C-EUC0603"))
    )
    (comp (ref "C516")
      (value "10n")
      (footprint "eagle-import:C0402")
      (libsource (lib "eagle-import") (part "C-EUC0402"))
    )
    (comp (ref "C517")
      (value "12p")
      (footprint "eagle-import:C0402")
      (libsource (lib "eagle-import") (part "C-EUC0402"))
    )
    (comp (ref "C518")
      (value "100n")
      (footprint "eagle-import:C0402")
      (libsource (lib "eagle-import") (part "C-EUC0402"))
    )
    (comp (ref "C519")
      (value "100n")
      (footprint "eagle-import:C0402")
      (libsource (lib "eagle-import") (part "C-EUC0402"))
    )
    (comp (ref "C520")
      (value "100n")
      (footprint "eagle-import:C0402")
      (libsource (lib "eagle-import") (part "C-EUC0402"))
    )
    (comp (ref "C521")
      (value "10u")
      (footprint "eagle-import:C0603")
      (libsource (lib "eagle-import") (part "C-EUC0603"))
    )
    (comp (ref "C522")
      (value "100n")
      (footprint "eagle-import:C0402")
      (libsource (lib "eagle-import") (part "C-EUC0402"))
    )
    (comp (ref "C523")
      (value "100n")
      (footprint "eagle-import:C0402")
      (libsource (lib "eagle-import") (part "C-EUC0402"))
    )
    (comp (ref "C524")
      (value "100n")
      (footprint "eagle-import:C0402")
      (libsource (lib "eagle-import") (part "C-EUC0402"))
    )
    (comp (ref "C525")
      (value "150p")
      (footprint "eagle-import:C0402")
      (libsource (lib "eagle-import") (part "C-EUC0402"))
    )
    (comp (ref "C526")
      (value "10n")
      (footprint "eagle-import:C0402")
      (libsource (lib "eagle-import") (part "C-EUC0402"))
    )
    (comp (ref "D501")
      (value "tbd")
      (footprint "eagle-import:DO41-10")
      (libsource (lib "eagle-import") (part "1N4004"))
    )
    (comp (ref "D502")
      (value "tbd")
      (footprint "eagle-import:DO41-10")
      (libsource (lib "eagle-import") (part "1N4004"))
    )
    (comp (ref "F501")
      (value "tbd")
      (footprint "eagle-import:R0805")
      (libsource (lib "eagle-import") (part "FUSE"))
    )
    (comp (ref "G501")
      (value "tbd")
      (footprint "eagle-import:2V60R")
      (libsource (lib "eagle-import") (part "2V60R"))
    )
    (comp (ref "L501")
      (value "2.2u")
      (footprint "eagle-import:L_WE3816")
      (libsource (lib "eagle-import") (part "LWE3816"))
    )
    (comp (ref "Q501")
      (value "E4JxA")
      (footprint "eagle-import:SOT23")
      (libsource (lib "eagle-import") (part "BSS84"))
    )
    (comp (ref "Q502")
      (value "BSS101")
      (footprint "eagle-import:TO92")
      (libsource (lib "eagle-import") (part "BSS101"))
    )
    (comp (ref "Q503")
      (value "BSS101")
      (footprint "eagle-import:TO92")
      (libsource (lib "eagle-import") (part "BSS101"))
    )
    (comp (ref "R501")
      (value "10k")
      (footprint "eagle-import:R0402")
      (libsource (lib "eagle-import") (part "R-EU_R0402"))
    )
    (comp (ref "R503")
      (value "330k")
      (footprint "eagle-import:R0402")
      (libsource (lib "eagle-import") (part "R-EU_R0402"))
    )
    (comp (ref "R504")
      (value "51k")
      (footprint "eagle-import:R0402")
      (libsource (lib "eagle-import") (part "R-EU_R0402"))
    )
    (comp (ref "R505")
      (value "20k")
      (footprint "eagle-import:R0402")
      (libsource (lib "eagle-import") (part "R-EU_R0402"))
    )
    (comp (ref "R506")
      (value "10k")
      (footprint "eagle-import:R0402")
      (libsource (lib "eagle-import") (part "R-EU_R0402"))
    )
    (comp (ref "R507")
      (value "1k")
      (footprint "eagle-import:R0402")
      (libsource (lib "eagle-import") (part "R-EU_R0402"))
    )
    (comp (ref "R508")
      (value "47k")
      (footprint "eagle-import:R0402")
      (libsource (lib "eagle-import") (part "R-EU_R0402"))
    )
    (comp (ref "R509")
      (value "47k")
      (footprint "eagle-import:R0402")
      (libsource (lib "eagle-import") (part "R-EU_R0402"))
    )
    (comp (ref "R510")
      (value "178k")
      (footprint "eagle-import:R0402")
      (libsource (lib "eagle-import") (part "R-EU_R0402"))
    )
    (comp (ref "R511")
      (value "100k")
      (footprint "eagle-import:R0402")
      (libsource (lib "eagle-import") (part "R-EU_R0402"))
    )
    (comp (ref "R512")
      (value "47k")
      (footprint "eagle-import:R0402")
      (libsource (lib "eagle-import") (part "R-EU_R0402"))
    )
    (comp (ref "R513")
      (value "47k")
      (footprint "eagle-import:R0402")
      (libsource (lib "eagle-import") (part "R-EU_R0402"))
    )
    (comp (ref "R514")
      (value "62k")
      (footprint "eagle-import:R0402")
      (libsource (lib "eagle-import") (part "R-EU_R0402"))
    )
    (comp (ref "S501")
      (value "tbd")
      (footprint "eagle-import:434121043816")
      (libsource (lib "eagle-import") (part "434121043816"))
    )
    (comp (ref "U501")
      (value "TLV70030SOT23-5")
      (footprint "eagle-import:SOT23-5")
      (libsource (lib "eagle-import") (part "TLV70030SOT23-5"))
    )
    (comp (ref "U502")
      (value "TPS61200")
      (footprint "eagle-import:QFN14_0.5MM_TH")
      (libsource (lib "eagle-import") (part "TPS61200"))
    )
    (comp (ref "U503")
      (value "TLV70030SOT23-5")
      (footprint "eagle-import:SOT23-5")
      (libsource (lib "eagle-import") (part "TLV70030SOT23-5"))
    )
    (comp (ref "U504")
      (value "TLV70030SOT23-5")
      (footprint "eagle-import:SOT23-5")
      (libsource (lib "eagle-import") (part "TLV70030SOT23-5"))
    )
  )
  (nets
    (net (code "1") (name "+3V_ANA") (class "Default")
      (node (ref "C201") (pin "1") (pinfunction "1_1") (pintype "passive"))
      (node (ref "C202") (pin "1") (pinfunction "1_1") (pintype "passive"))
      (node (ref "C203") (pin "1") (pinfunction "1_1") (pintype "passive"))
      (node (ref "C204") (pin "1") (pinfunction "1_1") (pintype "passive"))
      (node (ref "C205") (pin "1") (pinfunction "1_1") (pintype "passive"))
      (node (ref "C206") (pin "1") (pinfunction "1_1") (pintype "passive"))
      (node (ref "C514") (pin "1") (pinfunction "1_1") (pintype "passive"))
      (node (ref "C515") (pin "1") (pinfunction "1_1") (pintype "passive"))
      (node (ref "Q201") (pin "2") (pinfunction "D_2") (pintype "passive"))
      (node (ref "Q202") (pin "2") (pinfunction "D_2") (pintype "passive"))
      (node (ref "R206") (pin "2") (pinfunction "2_2") (pintype "passive"))
      (node (ref "U201") (pin "14") (pinfunction "VCC_14") (pintype "bidirectional"))
      (node (ref "U202") (pin "2") (pinfunction "VCC_2") (pintype "bidirectional"))
      (node (ref "U203") (pin "2") (pinfunction "VCC_2") (pintype "bidirectional"))
      (node (ref "U204") (pin "2") (pinfunction "VCC_2") (pintype "bidirectional"))
      (node (ref "U205") (pin "14") (pinfunction "VCC_14") (pintype "bidirectional"))
      (node (ref "U207") (pin "8") (pinfunction "VCC_8") (pintype "bidirectional"))
      (node (ref "U503") (pin "5") (pinfunction "OUT_5") (pintype "bidirectional"))
    )
    (net (code "2") (name "+3V_GPS") (class "Default")
      (node (ref "C319") (pin "2") (pinfunction "2_2") (pintype "passive"))
      (node (ref "C521") (pin "1") (pinfunction "1_1") (pintype "passive"))
      (node (ref "L305") (pin "1") (pinfunction "1_1") (pintype "passive"))
      (node (ref "L306") (pin "1") (pinfunction "1_1") (pintype "passive"))
      (node (ref "R308") (pin "1") (pinfunction "1_1") (pintype "passive"))
      (node (ref "U302") (pin "25") (pinfunction "V_DCDC_25") (pintype "bidirectional"))
      (node (ref "U504") (pin "5") (pinfunction "OUT_5") (pintype "bidirectional"))
    )
    (net (code "3") (name "+3V_MCU") (class "Default")
      (node (ref "C101") (pin "2") (pinfunction "2_2") (pintype "passive"))
      (node (ref "C102") (pin "2") (pinfunction "2_2") (pintype "passive"))
      (node (ref "C103") (pin "2") (pinfunction "2_2") (pintype "passive"))
      (node (ref "C104") (pin "2") (pinfunction "2_2") (pintype "passive"))
      (node (ref "C105") (pin "2") (pinfunction "2_2") (pintype "passive"))
      (node (ref "C106") (pin "2") (pinfunction "2_2") (pintype "passive"))
      (node (ref "C107") (pin "2") (pinfunction "2_2") (pintype "passive"))
      (node (ref "C108") (pin "2") (pinfunction "2_2") (pintype "passive"))
      (node (ref "C309") (pin "2") (pinfunction "2_2") (pintype "passive"))
      (node (ref "C315") (pin "2") (pinfunction "2_2") (pintype "passive"))
      (node (ref "C316") (pin "1") (pinfunction "1_1") (pintype "passive"))
      (node (ref "C413") (pin "1") (pinfunction "1_1") (pintype "passive"))
      (node (ref "C502") (pin "1") (pinfunction "1_1") (pintype "passive"))
      (node (ref "C503") (pin "1") (pinfunction "1_1") (pintype "passive"))
      (node (ref "C601") (pin "1") (pinfunction "1_1") (pintype "passive"))
      (node (ref "D601") (pin "C") (pinfunction "C_C") (pintype "passive"))
      (node (ref "J601") (pin "2") (pinfunction "16_2") (pintype "passive"))
      (node (ref "J602") (pin "4") (pinfunction "9_4") (pintype "passive"))
      (node (ref "L409") (pin "1") (pinfunction "1_1") (pintype "passive"))
      (node (ref "L410") (pin "2") (pinfunction "2_2") (pintype "passive"))
      (node (ref "R125") (pin "2") (pinfunction "2_2") (pintype "passive"))
      (node (ref "R601") (pin "2") (pinfunction "2_2") (pintype "passive"))
      (node (ref "R607") (pin "2") (pinfunction "2_2") (pintype "passive"))
      (node (ref "R608") (pin "2") (pinfunction "2_2") (pintype "passive"))
      (node (ref "U101") (pin "24") (pinfunction "VDD1_24") (pintype "bidirectional"))
      (node (ref "U101") (pin "36") (pinfunction "VDD2_36") (pintype "bidirectional"))
      (node (ref "U101") (pin "48") (pinfunction "VDD3_48") (pintype "bidirectional"))
      (node (ref "U101") (pin "9") (pinfunction "VDDA_9") (pintype "bidirectional"))
      (node (ref "U302") (pin "15") (pinfunction "VDD_IO_15") (pintype "bidirectional"))
      (node (ref "U302") (pin "29") (pinfunction "V_RUN_29") (pintype "bidirectional"))
      (node (ref "U302") (pin "42") (pinfunction "VDD_IO1_42") (pintype "bidirectional"))
      (node (ref "U501") (pin "5") (pinfunction "OUT_5") (pintype "bidirectional"))
      (node (ref "U601") (pin "3") (pinfunction "~{WP}_3") (pintype "input"))
      (node (ref "U601") (pin "7") (pinfunction "~{HOLD}_7") (pintype "input"))
      (node (ref "U601") (pin "8") (pinfunction "VCC_8") (pintype "power_in"))
    )
    (net (code "4") (name "BAT_SW") (class "Default")
      (node (ref "C504") (pin "1") (pinfunction "1_1") (pintype "passive"))
      (node (ref "C505") (pin "1") (pinfunction "1_1") (pintype "passive"))
      (node (ref "Q501") (pin "1") (pinfunction "G_1") (pintype "passive"))
      (node (ref "Q502") (pin "3") (pinfunction "D_3") (pintype "passive"))
      (node (ref "R501") (pin "2") (pinfunction "2_2") (pintype "passive"))
    )
    (net (code "5") (name "CS_PRESSURE") (class "Default")
      (node (ref "J601") (pin "14") (pinfunction "10_14") (pintype "passive"))
    )
    (net (code "6") (name "CS_RADIO") (class "Default")
      (node (ref "U101") (pin "2") (pinfunction "PC13_2") (pintype "bidirectional"))
      (node (ref "U401") (pin "16") (pinfunction "NSEL_16") (pintype "bidirectional"))
    )
    (net (code "7") (name "FRONTEND_UNKNOWN") (class "Default")
      (node (ref "C114") (pin "1") (pinfunction "1_1") (pintype "passive"))
      (node (ref "R106") (pin "1") (pinfunction "1_1") (pintype "passive"))
      (node (ref "R124") (pin "1") (pinfunction "1_1") (pintype "passive"))
      (node (ref "R206") (pin "1") (pinfunction "1_1") (pintype "passive"))
    )
    (net (code "8") (name "GND") (class "Default")
      (node (ref "A301") (pin "2") (pinfunction "GND_2") (pintype "bidirectional"))
      (node (ref "A301") (pin "3") (pinfunction "GND_3") (pintype "bidirectional"))
      (node (ref "C101") (pin "1") (pinfunction "1_1") (pintype "passive"))
      (node (ref "C102") (pin "1") (pinfunction "1_1") (pintype "passive"))
      (node (ref "C103") (pin "1") (pinfunction "1_1") (pintype "passive"))
      (node (ref "C104") (pin "1") (pinfunction "1_1") (pintype "passive"))
      (node (ref "C105") (pin "1") (pinfunction "1_1") (pintype "passive"))
      (node (ref "C106") (pin "1") (pinfunction "1_1") (pintype "passive"))
      (node (ref "C107") (pin "1") (pinfunction "1_1") (pintype "passive"))
      (node (ref "C108") (pin "1") (pinfunction "1_1") (pintype "passive"))
      (node (ref "C109") (pin "2") (pinfunction "2_2") (pintype "passive"))
      (node (ref "C110") (pin "2") (pinfunction "2_2") (pintype "passive"))
      (node (ref "C111") (pin "2") (pinfunction "2_2") (pintype "passive"))
      (node (ref "C112") (pin "2") (pinfunction "2_2") (pintype "passive"))
      (node (ref "C113") (pin "2") (pinfunction "2_2") (pintype "passive"))
      (node (ref "C114") (pin "2") (pinfunction "2_2") (pintype "passive"))
      (node (ref "C115") (pin "2") (pinfunction "2_2") (pintype "passive"))
      (node (ref "C116") (pin "1") (pinfunction "1_1") (pintype "passive"))
      (node (ref "C117") (pin "1") (pinfunction "1_1") (pintype "passive"))
      (node (ref "C118") (pin "1") (pinfunction "1_1") (pintype "passive"))
      (node (ref "C119") (pin "1") (pinfunction "1_1") (pintype "passive"))
      (node (ref "C120") (pin "1") (pinfunction "1_1") (pintype "passive"))
      (node (ref "C121") (pin "1") (pinfunction "1_1") (pintype "passive"))
      (node (ref "C122") (pin "1") (pinfunction "1_1") (pintype "passive"))
      (node (ref "C123") (pin "1") (pinfunction "1_1") (pintype "passive"))
      (node (ref "C124") (pin "1") (pinfunction "1_1") (pintype "passive"))
      (node (ref "C201") (pin "2") (pinfunction "2_2") (pintype "passive"))
      (node (ref "C202") (pin "2") (pinfunction "2_2") (pintype "passive"))
      (node (ref "C203") (pin "2") (pinfunction "2_2") (pintype "passive"))
      (node (ref "C204") (pin "2") (pinfunction "2_2") (pintype "passive"))
      (node (ref "C205") (pin "2") (pinfunction "2_2") (pintype "passive"))
      (node (ref "C206") (pin "2") (pinfunction "2_2") (pintype "passive"))
      (node (ref "C210") (pin "2") (pinfunction "2_2") (pintype "passive"))
      (node (ref "C211") (pin "2") (pinfunction "2_2") (pintype "passive"))
      (node (ref "C214") (pin "2") (pinfunction "2_2") (pintype "passive"))
      (node (ref "C218") (pin "2") (pinfunction "2_2") (pintype "passive"))
      (node (ref "C219") (pin "2") (pinfunction "2_2") (pintype "passive"))
      (node (ref "C220") (pin "2") (pinfunction "2_2") (pintype "passive"))
      (node (ref "C221") (pin "2") (pinfunction "2_2") (pintype "passive"))
      (node (ref "C301") (pin "2") (pinfunction "2_2") (pintype "passive"))
      (node (ref "C302") (pin "2") (pinfunction "2_2") (pintype "passive"))
      (node (ref "C303") (pin "1") (pinfunction "1_1") (pintype "passive"))
      (node (ref "C304") (pin "1") (pinfunction "1_1") (pintype "passive"))
      (node (ref "C305") (pin "1") (pinfunction "1_1") (pintype "passive"))
      (node (ref "C306") (pin "2") (pinfunction "2_2") (pintype "passive"))
      (node (ref "C307") (pin "2") (pinfunction "2_2") (pintype "passive"))
      (node (ref "C309") (pin "1") (pinfunction "1_1") (pintype "passive"))
      (node (ref "C310") (pin "2") (pinfunction "2_2") (pintype "passive"))
      (node (ref "C312") (pin "1") (pinfunction "1_1") (pintype "passive"))
      (node (ref "C313") (pin "1") (pinfunction "1_1") (pintype "passive"))
      (node (ref "C314") (pin "1") (pinfunction "1_1") (pintype "passive"))
      (node (ref "C315") (pin "1") (pinfunction "1_1") (pintype "passive"))
      (node (ref "C316") (pin "2") (pinfunction "2_2") (pintype "passive"))
      (node (ref "C317") (pin "1") (pinfunction "1_1") (pintype "passive"))
      (node (ref "C318") (pin "1") (pinfunction "1_1") (pintype "passive"))
      (node (ref "C319") (pin "1") (pinfunction "1_1") (pintype "passive"))
      (node (ref "C406") (pin "2") (pinfunction "2_2") (pintype "passive"))
      (node (ref "C407") (pin "2") (pinfunction "2_2") (pintype "passive"))
      (node (ref "C408") (pin "2") (pinfunction "2_2") (pintype "passive"))
      (node (ref "C409") (pin "1") (pinfunction "1_1") (pintype "passive"))
      (node (ref "C410") (pin "2") (pinfunction "2_2") (pintype "passive"))
      (node (ref "C411") (pin "2") (pinfunction "2_2") (pintype "passive"))
      (node (ref "C412") (pin "2") (pinfunction "2_2") (pintype "passive"))
      (node (ref "C413") (pin "2") (pinfunction "2_2") (pintype "passive"))
      (node (ref "C414") (pin "2") (pinfunction "2_2") (pintype "passive"))
      (node (ref "C415") (pin "2") (pinfunction "2_2") (pintype "passive"))
      (node (ref "C416") (pin "2") (pinfunction "2_2") (pintype "passive"))
      (node (ref "C417") (pin "2") (pinfunction "2_2") (pintype "passive"))
      (node (ref "C418") (pin "2") (pinfunction "2_2") (pintype "passive"))
      (node (ref "C419") (pin "2") (pinfunction "2_2") (pintype "passive"))
      (node (ref "C420") (pin "2") (pinfunction "2_2") (pintype "passive"))
      (node (ref "C421") (pin "2") (pinfunction "2_2") (pintype "passive"))
      (node (ref "C501") (pin "2") (pinfunction "2_2") (pintype "passive"))
      (node (ref "C502") (pin "2") (pinfunction "2_2") (pintype "passive"))
      (node (ref "C503") (pin "2") (pinfunction "2_2") (pintype "passive"))
      (node (ref "C506") (pin "2") (pinfunction "2_2") (pintype "passive"))
      (node (ref "C507") (pin "2") (pinfunction "2_2") (pintype "passive"))
      (node (ref "C508") (pin "2") (pinfunction "2_2") (pintype "passive"))
      (node (ref "C509") (pin "2") (pinfunction "2_2") (pintype "passive"))
      (node (ref "C510") (pin "2") (pinfunction "2_2") (pintype "passive"))
      (node (ref "C511") (pin "2") (pinfunction "2_2") (pintype "passive"))
      (node (ref "C512") (pin "2") (pinfunction "2_2") (pintype "passive"))
      (node (ref "C513") (pin "2") (pinfunction "2_2") (pintype "passive"))
      (node (ref "C514") (pin "2") (pinfunction "2_2") (pintype "passive"))
      (node (ref "C515") (pin "2") (pinfunction "2_2") (pintype "passive"))
      (node (ref "C516") (pin "2") (pinfunction "2_2") (pintype "passive"))
      (node (ref "C517") (pin "2") (pinfunction "2_2") (pintype "passive"))
      (node (ref "C518") (pin "2") (pinfunction "2_2") (pintype "passive"))
      (node (ref "C519") (pin "2") (pinfunction "2_2") (pintype "passive"))
      (node (ref "C520") (pin "2") (pinfunction "2_2") (pintype "passive"))
      (node (ref "C521") (pin "2") (pinfunction "2_2") (pintype "passive"))
      (node (ref "C522") (pin "2") (pinfunction "2_2") (pintype "passive"))
      (node (ref "C523") (pin "2") (pinfunction "2_2") (pintype "passive"))
      (node (ref "C524") (pin "2") (pinfunction "2_2") (pintype "passive"))
      (node (ref "C525") (pin "2") (pinfunction "2_2") (pintype "passive"))
      (node (ref "C526") (pin "2") (pinfunction "2_2") (pintype "passive"))
      (node (ref "C601") (pin "2") (pinfunction "2_2") (pintype "passive"))
      (node (ref "C603") (pin "1") (pinfunction "1_1") (pintype "passive"))
      (node (ref "C606") (pin "1") (pinfunction "1_1") (pintype "passive"))
      (node (ref "C607") (pin "1") (pinfunction "1_1") (pintype "passive"))
      (node (ref "D401") (pin "A") (pinfunction "A_A") (pintype "passive"))
      (node (ref "D501") (pin "A") (pinfunction "A_A") (pintype "passive"))
      (node (ref "D602") (pin "1") (pinfunction "A_1") (pintype "bidirectional"))
      (node (ref "D603") (pin "A") (pinfunction "A_A") (pintype "passive"))
      (node (ref "D604") (pin "A") (pinfunction "A_A") (pintype "passive"))
      (node (ref "D605") (pin "A") (pinfunction "A_A") (pintype "passive"))
      (node (ref "D606") (pin "A") (pinfunction "A_A") (pintype "passive"))
      (node (ref "D607") (pin "1") (pinfunction "A_1") (pintype "bidirectional"))
      (node (ref "G501") (pin "-") (pinfunction "-_-") (pintype "passive"))
      (node (ref "J201") (pin "1") (pinfunction "GND_1") (pintype "bidirectional"))
      (node (ref "J201") (pin "10") (pinfunction "GND_10") (pintype "bidirectional"))
      (node (ref "J201") (pin "12") (pinfunction "GND_12") (pintype "bidirectional"))
      (node (ref "J201") (pin "14") (pinfunction "GND_14") (pintype "bidirectional"))
      (node (ref "J201") (pin "15") (pinfunction "GND_15") (pintype "bidirectional"))
      (node (ref "J201") (pin "16") (pinfunction "GND_16") (pintype "bidirectional"))
      (node (ref "J201") (pin "3") (pinfunction "GND_3") (pintype "bidirectional"))
      (node (ref "J201") (pin "5") (pinfunction "GND_5") (pintype "bidirectional"))
      (node (ref "J201") (pin "7") (pinfunction "GND_7") (pintype "bidirectional"))
      (node (ref "J201") (pin "Z1") (pinfunction "GND_Z1") (pintype "bidirectional"))
      (node (ref "J201") (pin "Z2") (pinfunction "GND_Z2") (pintype "bidirectional"))
      (node (ref "J201") (pin "Z3") (pinfunction "GND_Z3") (pintype "bidirectional"))
      (node (ref "J201") (pin "Z4") (pinfunction "GND_Z4") (pintype "bidirectional"))
      (node (ref "J601") (pin "1") (pinfunction "1_1") (pintype "passive"))
      (node (ref "J601") (pin "12") (pinfunction "11_12") (pintype "passive"))
      (node (ref "J601") (pin "16") (pinfunction "9_16") (pintype "passive"))
      (node (ref "J602") (pin "1") (pinfunction "1_1") (pintype "passive"))
      (node (ref "J602") (pin "10") (pinfunction "6_10") (pintype "passive"))
      (node (ref "L304") (pin "1") (pinfunction "1_1") (pintype "passive"))
      (node (ref "L407") (pin "1") (pinfunction "1_1") (pintype "passive"))
      (node (ref "Q203") (pin "1") (pinfunction "S_1") (pintype "passive"))
      (node (ref "Q204") (pin "1") (pinfunction "S_1") (pintype "passive"))
      (node (ref "Q502") (pin "1") (pinfunction "S_1") (pintype "passive"))
      (node (ref "Q503") (pin "1") (pinfunction "S_1") (pintype "passive"))
      (node (ref "Q601") (pin "1") (pinfunction "S_1") (pintype "passive"))
      (node (ref "R124") (pin "2") (pinfunction "2_2") (pintype "passive"))
      (node (ref "R126") (pin "2") (pinfunction "2_2") (pintype "passive"))
      (node (ref "R209") (pin "2") (pinfunction "2_2") (pintype "passive"))
      (node (ref "R303") (pin "2") (pinfunction "2_2") (pintype "passive"))
      (node (ref "R401") (pin "1") (pinfunction "1_1") (pintype "passive"))
      (node (ref "R504") (pin "1") (pinfunction "1_1") (pintype "passive"))
      (node (ref "R511") (pin "2") (pinfunction "2_2") (pintype "passive"))
      (node (ref "R512") (pin "1") (pinfunction "1_1") (pintype "passive"))
      (node (ref "R513") (pin "1") (pinfunction "1_1") (pintype "passive"))
      (node (ref "R514") (pin "2") (pinfunction "2_2") (pintype "passive"))
      (node (ref "R603") (pin "1") (pinfunction "1_1") (pintype "passive"))
      (node (ref "R604") (pin "1") (pinfunction "1_1") (pintype "passive"))
      (node (ref "U101") (pin "23") (pinfunction "VSS1_23") (pintype "bidirectional"))
      (node (ref "U101") (pin "35") (pinfunction "VSS2_35") (pintype "bidirectional"))
      (node (ref "U101") (pin "47") (pinfunction "VSS3_47") (pintype "bidirectional"))
      (node (ref "U101") (pin "8") (pinfunction "VSSA_8") (pintype "bidirectional"))
      (node (ref "U201") (pin "7") (pinfunction "GND_7") (pintype "bidirectional"))
      (node (ref "U202") (pin "3") (pinfunction "GND_3") (pintype "bidirectional"))
      (node (ref "U202") (pin "4") (pinfunction "NC_4") (pintype "bidirectional"))
      (node (ref "U203") (pin "3") (pinfunction "GND_3") (pintype "bidirectional"))
      (node (ref "U203") (pin "4") (pinfunction "NC_4") (pintype "bidirectional"))
      (node (ref "U204") (pin "3") (pinfunction "GND_3") (pintype "bidirectional"))
      (node (ref "U204") (pin "4") (pinfunction "NC_4") (pintype "bidirectional"))
      (node (ref "U205") (pin "7") (pinfunction "GND_7") (pintype "bidirectional"))
      (node (ref "U206") (pin "2") (pinfunction "GND_2") (pintype "bidirectional"))
      (node (ref "U207") (pin "4") (pinfunction "GND_4") (pintype "bidirectional"))
      (node (ref "U208") (pin "3") (pinfunction "B_3") (pintype "bidirectional"))
      (node (ref "U301") (pin "1") (pinfunction "GND1_1") (pintype "bidirectional"))
      (node (ref "U301") (pin "2") (pinfunction "GND2_2") (pintype "bidirectional"))
      (node (ref "U302") (pin "12") (pinfunction "VDD_USB_12") (pintype "bidirectional"))
      (node (ref "U303") (pin "1") (pinfunction "GND1_1") (pintype "bidirectional"))
      (node (ref "U303") (pin "2") (pinfunction "GND2_2") (pintype "bidirectional"))
      (node (ref "U303") (pin "3") (pinfunction "GND3_3") (pintype "bidirectional"))
      (node (ref "U304") (pin "1") (pinfunction "GND1_1") (pintype "bidirectional"))
      (node (ref "U304") (pin "2") (pinfunction "GND2_2") (pintype "bidirectional"))
      (node (ref "U304") (pin "4") (pinfunction "GND3_4") (pintype "bidirectional"))
      (node (ref "U304") (pin "5") (pinfunction "GND4_5") (pintype "bidirectional"))
      (node (ref "U401") (pin "20") (pinfunction "SDN_20") (pintype "bidirectional"))
      (node (ref "U401") (pin "21") (pinfunction "EP_21") (pintype "bidirectional"))
      (node (ref "U501") (pin "2") (pinfunction "GND_2") (pintype "bidirectional"))
      (node (ref "U502") (pin "4") (pinfunction "PGND_4") (pintype "bidirectional"))
      (node (ref "U502") (pin "9") (pinfunction "GND_9") (pintype "bidirectional"))
      (node (ref "U502") (pin "TH1") (pinfunction "PGND_TH1") (pintype "bidirectional"))
      (node (ref "U502") (pin "TH2") (pinfunction "PGND_TH2") (pintype "bidirectional"))
      (node (ref "U502") (pin "TH3") (pinfunction "PGND_TH3") (pintype "bidirectional"))
      (node (ref "U502") (pin "TH4") (pinfunction "PGND_TH4") (pintype "bidirectional"))
      (node (ref "U502") (pin "TH5") (pinfunction "PGND_TH5") (pintype "bidirectional"))
      (node (ref "U503") (pin "2") (pinfunction "GND_2") (pintype "bidirectional"))
      (node (ref "U504") (pin "2") (pinfunction "GND_2") (pintype "bidirectional"))
      (node (ref "U601") (pin "4") (pinfunction "GND_4") (pintype "power_in"))
      (node (ref "X101") (pin "1") (pinfunction "GND_1") (pintype "bidirectional"))
      (node (ref "X101") (pin "4") (pinfunction "GND_4") (pintype "bidirectional"))
      (node (ref "X301") (pin "4") (pinfunction "VCC_4") (pintype "bidirectional"))
    )
    (net (code "9") (name "GPS_CLK") (class "Default")
      (node (ref "R309") (pin "2") (pinfunction "2_2") (pintype "passive"))
      (node (ref "U302") (pin "49") (pinfunction "XTAL_I_49") (pintype "bidirectional"))
      (node (ref "X301") (pin "3") (pinfunction "OUT_3") (pintype "bidirectional"))
    )
    (net (code "10") (name "GPS_RESETN") (class "Default")
      (node (ref "R308") (pin "2") (pinfunction "2_2") (pintype "passive"))
      (node (ref "U302") (pin "23") (pinfunction "V_RESET_23") (pintype "bidirectional"))
    )
    (net (code "11") (name "GPS_RESET_N") (class "Default")
      (node (ref "C115") (pin "1") (pinfunction "1_1") (pintype "passive"))
      (node (ref "R123") (pin "1") (pinfunction "1_1") (pintype "passive"))
    )
    (net (code "12") (name "GPS_RX") (class "Default")
      (node (ref "R307") (pin "2") (pinfunction "2_2") (pintype "passive"))
      (node (ref "U101") (pin "30") (pinfunction "PA9_30") (pintype "bidirectional"))
    )
    (net (code "13") (name "GPS_TX") (class "Default")
      (node (ref "R306") (pin "2") (pinfunction "2_2") (pintype "passive"))
      (node (ref "U101") (pin "31") (pinfunction "PA10_31") (pintype "bidirectional"))
    )
    (net (code "14") (name "HEAT_HUM1") (class "Default")
      (node (ref "C217") (pin "1") (pinfunction "1_1") (pintype "passive"))
      (node (ref "R110") (pin "1") (pinfunction "1_1") (pintype "passive"))
      (node (ref "R213") (pin "2") (pinfunction "2_2") (pintype "passive"))
      (node (ref "U206") (pin "1") (pinfunction "MCU1_1") (pintype "bidirectional"))
    )
    (net (code "15") (name "HEAT_HUM2") (class "Default")
      (node (ref "C123") (pin "2") (pinfunction "2_2") (pintype "passive"))
      (node (ref "R114") (pin "1") (pinfunction "1_1") (pintype "passive"))
      (node (ref "U206") (pin "3") (pinfunction "MCU2_3") (pintype "bidirectional"))
    )
    (net (code "16") (name "HEAT_REF") (class "Default")
      (node (ref "C419") (pin "1") (pinfunction "1_1") (pintype "passive"))
      (node (ref "Q203") (pin "2") (pinfunction "G_2") (pintype "passive"))
      (node (ref "Q204") (pin "2") (pinfunction "G_2") (pintype "passive"))
      (node (ref "R406") (pin "2") (pinfunction "2_2") (pintype "passive"))
    )
    (net (code "17") (name "LED_GRN") (class "Default")
      (node (ref "C121") (pin "2") (pinfunction "2_2") (pintype "passive"))
      (node (ref "D609") (pin "C") (pinfunction "C_C") (pintype "passive"))
      (node (ref "L101") (pin "2") (pinfunction "2_2") (pintype "passive"))
    )
    (net (code "18") (name "LED_RED") (class "Default")
      (node (ref "C122") (pin "2") (pinfunction "2_2") (pintype "passive"))
      (node (ref "D608") (pin "C") (pinfunction "C_C") (pintype "passive"))
      (node (ref "L102") (pin "2") (pinfunction "2_2") (pintype "passive"))
    )
    (net (code "19") (name "MCU_RST") (class "Default")
      (node (ref "D604") (pin "C") (pinfunction "C_C") (pintype "passive"))
      (node (ref "J602") (pin "7") (pinfunction "4_7") (pintype "passive"))
      (node (ref "R101") (pin "1") (pinfunction "1_1") (pintype "passive"))
    )
    (net (code "20") (name "MEAS_OUT") (class "Default")
      (node (ref "R102") (pin "1") (pinfunction "1_1") (pintype "passive"))
      (node (ref "U208") (pin "4") (pinfunction "Y_4") (pintype "output"))
    )
    (net (code "21") (name "NFC_EN") (class "Default")
      (node (ref "D607") (pin "2") (pinfunction "K_2") (pintype "bidirectional"))
      (node (ref "R506") (pin "1") (pinfunction "1_1") (pintype "passive"))
      (node (ref "R510") (pin "1") (pinfunction "1_1") (pintype "passive"))
    )
    (net (code "22") (name "NFC_IN1") (class "Default")
      (node (ref "C603") (pin "2") (pinfunction "2_2") (pintype "passive"))
      (node (ref "D601") (pin "A") (pinfunction "A_A") (pintype "passive"))
      (node (ref "R602") (pin "1") (pinfunction "1_1") (pintype "passive"))
      (node (ref "U101") (pin "32") (pinfunction "PA11_32") (pintype "bidirectional"))
    )
    (net (code "23") (name "NFC_IN2") (class "Default")
      (node (ref "C525") (pin "1") (pinfunction "1_1") (pintype "passive"))
      (node (ref "R510") (pin "2") (pinfunction "2_2") (pintype "passive"))
      (node (ref "R514") (pin "1") (pinfunction "1_1") (pintype "passive"))
      (node (ref "U101") (pin "10") (pinfunction "PA0_10") (pintype "bidirectional"))
    )
    (net (code "24") (name "NFC_OUT") (class "Default")
      (node (ref "R606") (pin "1") (pinfunction "1_1") (pintype "passive"))
      (node (ref "U101") (pin "18") (pinfunction "PB0_18") (pintype "bidirectional"))
    )
    (net (code "25") (name "Net-(A301-ANT)") (class "Default")
      (node (ref "A301") (pin "1") (pinfunction "ANT_1") (pintype "bidirectional"))
      (node (ref "C310") (pin "1") (pinfunction "1_1") (pintype "passive"))
      (node (ref "R304") (pin "2") (pinfunction "2_2") (pintype "passive"))
    )
    (net (code "26") (name "Net-(C207-Pad2)") (class "Default")
      (node (ref "C207") (pin "2") (pinfunction "2_2") (pintype "passive"))
      (node (ref "R210") (pin "1") (pinfunction "1_1") (pintype "passive"))
    )
    (net (code "27") (name "Net-(C208-Pad2)") (class "Default")
      (node (ref "C208") (pin "2") (pinfunction "2_2") (pintype "passive"))
      (node (ref "R211") (pin "2") (pinfunction "2_2") (pintype "passive"))
    )
    (net (code "28") (name "Net-(C215-Pad1)") (class "Default")
      (node (ref "C215") (pin "1") (pinfunction "1_1") (pintype "passive"))
      (node (ref "R214") (pin "2") (pinfunction "2_2") (pintype "passive"))
    )
    (net (code "29") (name "Net-(C216-Pad1)") (class "Default")
      (node (ref "C216") (pin "1") (pinfunction "1_1") (pintype "passive"))
      (node (ref "R215") (pin "1") (pinfunction "1_1") (pintype "passive"))
    )
    (net (code "30") (name "Net-(C302-Pad1)") (class "Default")
      (node (ref "C302") (pin "1") (pinfunction "1_1") (pintype "passive"))
      (node (ref "L306") (pin "2") (pinfunction "2_2") (pintype "passive"))
      (node (ref "X301") (pin "1") (pinfunction "GND1_1") (pintype "bidirectional"))
      (node (ref "X301") (pin "2") (pinfunction "GND1_2") (pintype "bidirectional"))
    )
    (net (code "31") (name "Net-(C308-Pad1)") (class "Default")
      (node (ref "C308") (pin "1") (pinfunction "1_1") (pintype "passive"))
      (node (ref "L301") (pin "1") (pinfunction "1_1") (pintype "passive"))
      (node (ref "L303") (pin "2") (pinfunction "2_2") (pintype "passive"))
    )
    (net (code "32") (name "Net-(C402-Pad1)") (class "Default")
      (node (ref "C402") (pin "1") (pinfunction "1_1") (pintype "passive"))
      (node (ref "L401") (pin "2") (pinfunction "2_2") (pintype "passive"))
      (node (ref "R401") (pin "2") (pinfunction "2_2") (pintype "passive"))
    )
    (net (code "33") (name "Net-(C402-Pad2)") (class "Default")
      (node (ref "C402") (pin "2") (pinfunction "2_2") (pintype "passive"))
      (node (ref "C404") (pin "1") (pinfunction "1_1") (pintype "passive"))
      (node (ref "D401") (pin "C") (pinfunction "C_C") (pintype "passive"))
      (node (ref "L401") (pin "1") (pinfunction "1_1") (pintype "passive"))
      (node (ref "L405") (pin "2") (pinfunction "2_2") (pintype "passive"))
    )
    (net (code "34") (name "Net-(C403-Pad1)") (class "Default")
      (node (ref "C403") (pin "1") (pinfunction "1_1") (pintype "passive"))
      (node (ref "C405") (pin "2") (pinfunction "2_2") (pintype "passive"))
      (node (ref "L402") (pin "2") (pinfunction "2_2") (pintype "passive"))
      (node (ref "L407") (pin "2") (pinfunction "2_2") (pintype "passive"))
    )
    (net (code "35") (name "Net-(C403-Pad2)") (class "Default")
      (node (ref "C403") (pin "2") (pinfunction "2_2") (pintype "passive"))
      (node (ref "C406") (pin "1") (pinfunction "1_1") (pintype "passive"))
      (node (ref "L403") (pin "1") (pinfunction "1_1") (pintype "passive"))
    )
    (net (code "36") (name "Net-(C407-Pad1)") (class "Default")
      (node (ref "C407") (pin "1") (pinfunction "1_1") (pintype "passive"))
      (node (ref "L403") (pin "2") (pinfunction "2_2") (pintype "passive"))
      (node (ref "L404") (pin "1") (pinfunction "1_1") (pintype "passive"))
    )
    (net (code "37") (name "Net-(C408-Pad1)") (class "Default")
      (node (ref "C408") (pin "1") (pinfunction "1_1") (pintype "passive"))
      (node (ref "L404") (pin "2") (pinfunction "2_2") (pintype "passive"))
      (node (ref "L405") (pin "1") (pinfunction "1_1") (pintype "passive"))
    )
    (net (code "38") (name "Net-(C412-Pad1)") (class "Default")
      (node (ref "C412") (pin "1") (pinfunction "1_1") (pintype "passive"))
      (node (ref "L406") (pin "1") (pinfunction "1_1") (pintype "passive"))
    )
    (net (code "39") (name "Net-(C418-Pad1)") (class "Default")
      (node (ref "C418") (pin "1") (pinfunction "1_1") (pintype "passive"))
      (node (ref "L408") (pin "1") (pinfunction "1_1") (pintype "passive"))
      (node (ref "R405") (pin "1") (pinfunction "1_1") (pintype "passive"))
    )
    (net (code "40") (name "Net-(C602-Pad2)") (class "Default")
      (node (ref "C602") (pin "2") (pinfunction "2_2") (pintype "passive"))
      (node (ref "R601") (pin "1") (pinfunction "1_1") (pintype "passive"))
      (node (ref "R602") (pin "2") (pinfunction "2_2") (pintype "passive"))
      (node (ref "R604") (pin "2") (pinfunction "2_2") (pintype "passive"))
    )
    (net (code "41") (name "Net-(D502-PadA)") (class "Default")
      (node (ref "D502") (pin "A") (pinfunction "A_A") (pintype "passive"))
      (node (ref "R506") (pin "2") (pinfunction "2_2") (pintype "passive"))
    )
    (net (code "42") (name "Net-(D602-K)") (class "Default")
      (node (ref "C602") (pin "1") (pinfunction "1_1") (pintype "passive"))
      (node (ref "D602") (pin "2") (pinfunction "K_2") (pintype "bidirectional"))
      (node (ref "D603") (pin "C") (pinfunction "C_C") (pintype "passive"))
      (node (ref "R603") (pin "2") (pinfunction "2_2") (pintype "passive"))
    )
    (net (code "43") (name "Net-(D602-M)") (class "Default")
      (node (ref "C604") (pin "1") (pinfunction "1_1") (pintype "passive"))
      (node (ref "C604") (pin "2") (pinfunction "2_2") (pintype "passive"))
      (node (ref "C605") (pin "1") (pinfunction "1_1") (pintype "passive"))
      (node (ref "C605") (pin "2") (pinfunction "2_2") (pintype "passive"))
      (node (ref "D602") (pin "3") (pinfunction "M_3") (pintype "bidirectional"))
      (node (ref "D607") (pin "3") (pinfunction "M_3") (pintype "bidirectional"))
      (node (ref "R605") (pin "2") (pinfunction "2_2") (pintype "passive"))
    )
    (net (code "44") (name "Net-(D608-PadA)") (class "Default")
      (node (ref "D608") (pin "A") (pinfunction "A_A") (pintype "passive"))
      (node (ref "R607") (pin "1") (pinfunction "1_1") (pintype "passive"))
    )
    (net (code "45") (name "Net-(D609-PadA)") (class "Default")
      (node (ref "D609") (pin "A") (pinfunction "A_A") (pintype "passive"))
      (node (ref "R608") (pin "1") (pinfunction "1_1") (pintype "passive"))
    )
    (net (code "46") (name "Net-(F501-Pad1)") (class "Default")
      (node (ref "F501") (pin "1") (pinfunction "1_1") (pintype "passive"))
      (node (ref "G501") (pin "+") (pinfunction "+_+") (pintype "passive"))
    )
    (net (code "47") (name "Net-(J201B-1)") (class "Default")
      (node (ref "C217") (pin "2") (pinfunction "2_2") (pintype "passive"))
      (node (ref "J201") (pin "8") (pinfunction "1_8") (pintype "passive"))
      (node (ref "R213") (pin "1") (pinfunction "1_1") (pintype "passive"))
      (node (ref "R216") (pin "2") (pinfunction "2_2") (pintype "passive"))
      (node (ref "R217") (pin "2") (pinfunction "2_2") (pintype "passive"))
      (node (ref "R218") (pin "2") (pinfunction "2_2") (pintype "passive"))
      (node (ref "U206") (pin "6") (pinfunction "SENSE3_6") (pintype "bidirectional"))
    )
    (net (code "48") (name "Net-(J201C-1)") (class "Default")
      (node (ref "C208") (pin "1") (pinfunction "1_1") (pintype "passive"))
      (node (ref "C209") (pin "1") (pinfunction "1_1") (pintype "passive"))
      (node (ref "C210") (pin "1") (pinfunction "1_1") (pintype "passive"))
      (node (ref "C211") (pin "1") (pinfunction "1_1") (pintype "passive"))
      (node (ref "C213") (pin "1") (pinfunction "1_1") (pintype "passive"))
      (node (ref "J201") (pin "4") (pinfunction "1_4") (pintype "passive"))
      (node (ref "Q202") (pin "3") (pinfunction "S_3") (pintype "passive"))
      (node (ref "R204") (pin "2") (pinfunction "2_2") (pintype "passive"))
      (node (ref "R205") (pin "2") (pinfunction "2_2") (pintype "passive"))
      (node (ref "R212") (pin "2") (pinfunction "2_2") (pintype "passive"))
      (node (ref "U205") (pin "1") (pinfunction "A_1") (pintype "bidirectional"))
    )
    (net (code "49") (name "Net-(J201C-2)") (class "Default")
      (node (ref "J201") (pin "6") (pinfunction "2_6") (pintype "passive"))
      (node (ref "U203") (pin "5") (pinfunction "COM_5") (pintype "bidirectional"))
    )
    (net (code "50") (name "Net-(J201D-HYG_TEMP)") (class "Default")
      (node (ref "J201") (pin "11") (pinfunction "HYG_TEMP_11") (pintype "passive"))
      (node (ref "U201") (pin "8") (pinfunction "NO_8") (pintype "bidirectional"))
    )
    (net (code "51") (name "Net-(J201D-TEMP)") (class "Default")
      (node (ref "J201") (pin "2") (pinfunction "TEMP_2") (pintype "passive"))
      (node (ref "U201") (pin "11") (pinfunction "NO_11") (pintype "bidirectional"))
    )
    (net (code "52") (name "Net-(J201D-TEMP_COM)") (class "Default")
      (node (ref "C207") (pin "1") (pinfunction "1_1") (pintype "passive"))
      (node (ref "C212") (pin "1") (pinfunction "1_1") (pintype "passive"))
      (node (ref "C220") (pin "1") (pinfunction "1_1") (pintype "passive"))
      (node (ref "C221") (pin "1") (pinfunction "1_1") (pintype "passive"))
      (node (ref "J201") (pin "13") (pinfunction "TEMP_COM_13") (pintype "passive"))
      (node (ref "Q201") (pin "3") (pinfunction "S_3") (pintype "passive"))
      (node (ref "R201") (pin "2") (pinfunction "2_2") (pintype "passive"))
      (node (ref "R202") (pin "2") (pinfunction "2_2") (pintype "passive"))
      (node (ref "R203") (pin "2") (pinfunction "2_2") (pintype "passive"))
      (node (ref "R207") (pin "1") (pinfunction "1_1") (pintype "passive"))
      (node (ref "R208") (pin "1") (pinfunction "1_1") (pintype "passive"))
      (node (ref "U205") (pin "13") (pinfunction "A_13") (pintype "bidirectional"))
    )
    (net (code "53") (name "Net-(Q203-D)") (class "Default")
      (node (ref "Q203") (pin "3") (pinfunction "D_3") (pintype "passive"))
      (node (ref "R201") (pin "1") (pinfunction "1_1") (pintype "passive"))
      (node (ref "R202") (pin "1") (pinfunction "1_1") (pintype "passive"))
      (node (ref "R203") (pin "1") (pinfunction "1_1") (pintype "passive"))
    )
    (net (code "54") (name "Net-(Q204-D)") (class "Default")
      (node (ref "Q204") (pin "3") (pinfunction "D_3") (pintype "passive"))
      (node (ref "R204") (pin "1") (pinfunction "1_1") (pintype "passive"))
      (node (ref "R205") (pin "1") (pinfunction "1_1") (pintype "passive"))
    )
    (net (code "55") (name "Net-(Q502-G)") (class "Default")
      (node (ref "C517") (pin "1") (pinfunction "1_1") (pintype "passive"))
      (node (ref "C518") (pin "1") (pinfunction "1_1") (pintype "passive"))
      (node (ref "C519") (pin "1") (pinfunction "1_1") (pintype "passive"))
      (node (ref "D502") (pin "C") (pinfunction "C_C") (pintype "passive"))
      (node (ref "Q502") (pin "2") (pinfunction "G_2") (pintype "passive"))
      (node (ref "Q503") (pin "3") (pinfunction "D_3") (pintype "passive"))
      (node (ref "R505") (pin "1") (pinfunction "1_1") (pintype "passive"))
      (node (ref "R507") (pin "1") (pinfunction "1_1") (pintype "passive"))
      (node (ref "R509") (pin "2") (pinfunction "2_2") (pintype "passive"))
    )
    (net (code "56") (name "Net-(Q601-D)") (class "Default")
      (node (ref "Q601") (pin "3") (pinfunction "D_3") (pintype "passive"))
      (node (ref "R605") (pin "1") (pinfunction "1_1") (pintype "passive"))
    )
    (net (code "57") (name "Net-(Q601-G)") (class "Default")
      (node (ref "Q601") (pin "2") (pinfunction "G_2") (pintype "passive"))
      (node (ref "R606") (pin "2") (pinfunction "2_2") (pintype "passive"))
    )
    (net (code "58") (name "Net-(R507-Pad2)") (class "Default")
      (node (ref "R507") (pin "2") (pinfunction "2_2") (pintype "passive"))
      (node (ref "S501") (pin "2") (pinfunction "2_2") (pintype "passive"))
    )
    (net (code "59") (name "Net-(U101A-PA1)") (class "Default")
      (node (ref "R102") (pin "2") (pinfunction "2_2") (pintype "passive"))
      (node (ref "U101") (pin "11") (pinfunction "PA1_11") (pintype "bidirectional"))
    )
    (net (code "60") (name "Net-(U101A-PA2)") (class "Default")
      (node (ref "R104") (pin "2") (pinfunction "2_2") (pintype "passive"))
      (node (ref "U101") (pin "12") (pinfunction "PA2_12") (pintype "bidirectional"))
    )
    (net (code "61") (name "Net-(U101A-PA4)") (class "Default")
      (node (ref "R106") (pin "2") (pinfunction "2_2") (pintype "passive"))
      (node (ref "U101") (pin "14") (pinfunction "PA4_14") (pintype "bidirectional"))
    )
    (net (code "62") (name "Net-(U101A-PA7)") (class "Default")
      (node (ref "R110") (pin "2") (pinfunction "2_2") (pintype "passive"))
      (node (ref "U101") (pin "17") (pinfunction "PA7_17") (pintype "bidirectional"))
    )
    (net (code "63") (name "Net-(U101A-PA8)") (class "Default")
      (node (ref "R112") (pin "2") (pinfunction "2_2") (pintype "passive"))
      (node (ref "U101") (pin "29") (pinfunction "PA8_29") (pintype "bidirectional"))
    )
    (net (code "64") (name "Net-(U101A-PA12)") (class "Default")
      (node (ref "R117") (pin "2") (pinfunction "2_2") (pintype "passive"))
      (node (ref "U101") (pin "33") (pinfunction "PA12_33") (pintype "bidirectional"))
    )
    (net (code "65") (name "Net-(U101A-PA13)") (class "Default")
      (node (ref "R119") (pin "2") (pinfunction "2_2") (pintype "passive"))
      (node (ref "U101") (pin "34") (pinfunction "PA13_34") (pintype "bidirectional"))
    )
    (net (code "66") (name "Net-(U101A-PA14)") (class "Default")
      (node (ref "R121") (pin "2") (pinfunction "2_2") (pintype "passive"))
      (node (ref "U101") (pin "37") (pinfunction "PA14_37") (pintype "bidirectional"))
    )
    (net (code "67") (name "Net-(U101A-PA15)") (class "Default")
      (node (ref "R123") (pin "2") (pinfunction "2_2") (pintype "passive"))
      (node (ref "U101") (pin "38") (pinfunction "PA15_38") (pintype "bidirectional"))
    )
    (net (code "68") (name "Net-(U101B-PB1)") (class "Default")
      (node (ref "R103") (pin "2") (pinfunction "2_2") (pintype "passive"))
      (node (ref "U101") (pin "19") (pinfunction "PB1_19") (pintype "bidirectional"))
    )
    (net (code "69") (name "Net-(U101B-PB3)") (class "Default")
      (node (ref "R105") (pin "2") (pinfunction "2_2") (pintype "passive"))
      (node (ref "U101") (pin "39") (pinfunction "PB3_39") (pintype "bidirectional"))
    )
    (net (code "70") (name "Net-(U101B-PB4)") (class "Default")
      (node (ref "R107") (pin "2") (pinfunction "2_2") (pintype "passive"))
      (node (ref "U101") (pin "40") (pinfunction "PB4_40") (pintype "bidirectional"))
    )
    (net (code "71") (name "Net-(U101B-PB5)") (class "Default")
      (node (ref "R108") (pin "2") (pinfunction "2_2") (pintype "passive"))
      (node (ref "U101") (pin "41") (pinfunction "PB5_41") (pintype "bidirectional"))
    )
    (net (code "72") (name "Net-(U101B-PB6)") (class "Default")
      (node (ref "R109") (pin "2") (pinfunction "2_2") (pintype "passive"))
      (node (ref "U101") (pin "42") (pinfunction "PB6_42") (pintype "bidirectional"))
    )
    (net (code "73") (name "Net-(U101B-PB7)") (class "Default")
      (node (ref "L101") (pin "1") (pinfunction "1_1") (pintype "passive"))
      (node (ref "U101") (pin "43") (pinfunction "PB7_43") (pintype "bidirectional"))
    )
    (net (code "74") (name "Net-(U101B-PB8)") (class "Default")
      (node (ref "L102") (pin "1") (pinfunction "1_1") (pintype "passive"))
      (node (ref "U101") (pin "45") (pinfunction "PB8_45") (pintype "bidirectional"))
    )
    (net (code "75") (name "Net-(U101B-PB9)") (class "Default")
      (node (ref "R114") (pin "2") (pinfunction "2_2") (pintype "passive"))
      (node (ref "R126") (pin "1") (pinfunction "1_1") (pintype "passive"))
      (node (ref "U101") (pin "46") (pinfunction "PB9_46") (pintype "bidirectional"))
    )
    (net (code "76") (name "Net-(U101B-PB10)") (class "Default")
      (node (ref "R115") (pin "2") (pinfunction "2_2") (pintype "passive"))
      (node (ref "U101") (pin "21") (pinfunction "PB10_21") (pintype "bidirectional"))
    )
    (net (code "77") (name "Net-(U101B-PB11)") (class "Default")
      (node (ref "R116") (pin "2") (pinfunction "2_2") (pintype "passive"))
      (node (ref "U101") (pin "22") (pinfunction "PB11_22") (pintype "bidirectional"))
    )
    (net (code "78") (name "Net-(U101B-PB12)") (class "Default")
      (node (ref "R118") (pin "2") (pinfunction "2_2") (pintype "passive"))
      (node (ref "U101") (pin "25") (pinfunction "PB12_25") (pintype "bidirectional"))
    )
    (net (code "79") (name "Net-(U101B-PB13)") (class "Default")
      (node (ref "R120") (pin "2") (pinfunction "2_2") (pintype "passive"))
      (node (ref "R122") (pin "2") (pinfunction "2_2") (pintype "passive"))
      (node (ref "U101") (pin "26") (pinfunction "PB13_26") (pintype "bidirectional"))
    )
    (net (code "80") (name "Net-(U101C-NRST)") (class "Default")
      (node (ref "C112") (pin "1") (pinfunction "1_1") (pintype "passive"))
      (node (ref "R101") (pin "2") (pinfunction "2_2") (pintype "passive"))
      (node (ref "U101") (pin "7") (pinfunction "NRST_7") (pintype "bidirectional"))
    )
    (net (code "81") (name "Net-(U101C-PD0{slash}OSC_O)") (class "Default")
      (node (ref "C109") (pin "1") (pinfunction "1_1") (pintype "passive"))
      (node (ref "U101") (pin "5") (pinfunction "PD0/OSC_O_5") (pintype "bidirectional"))
      (node (ref "X101") (pin "2") (pinfunction "XIN_2") (pintype "bidirectional"))
    )
    (net (code "82") (name "Net-(U101C-PD1{slash}OSC_I)") (class "Default")
      (node (ref "C110") (pin "1") (pinfunction "1_1") (pintype "passive"))
      (node (ref "U101") (pin "6") (pinfunction "PD1/OSC_I_6") (pintype "bidirectional"))
      (node (ref "X101") (pin "3") (pinfunction "XOUT_3") (pintype "bidirectional"))
    )
    (net (code "83") (name "Net-(U101C-VBAT)") (class "Default")
      (node (ref "C111") (pin "1") (pinfunction "1_1") (pintype "passive"))
      (node (ref "U101") (pin "1") (pinfunction "VBAT_1") (pintype "bidirectional"))
    )
    (net (code "84") (name "Net-(U201B-COM)") (class "Default")
      (node (ref "R224") (pin "1") (pinfunction "1_1") (pintype "passive"))
      (node (ref "U201") (pin "10") (pinfunction "COM_10") (pintype "bidirectional"))
      (node (ref "U201") (pin "2") (pinfunction "COM_2") (pintype "bidirectional"))
      (node (ref "U201") (pin "4") (pinfunction "COM_4") (pintype "bidirectional"))
      (node (ref "U201") (pin "9") (pinfunction "COM_9") (pintype "bidirectional"))
      (node (ref "U207") (pin "7") (pinfunction "Y_7") (pintype "bidirectional"))
    )
    (net (code "85") (name "Net-(U201B-NO)") (class "Default")
      (node (ref "R208") (pin "2") (pinfunction "2_2") (pintype "passive"))
      (node (ref "U201") (pin "1") (pinfunction "NO_1") (pintype "bidirectional"))
    )
    (net (code "86") (name "Net-(U201C-NO)") (class "Default")
      (node (ref "R207") (pin "2") (pinfunction "2_2") (pintype "passive"))
      (node (ref "U201") (pin "3") (pinfunction "NO_3") (pintype "bidirectional"))
    )
    (net (code "87") (name "Net-(U202B-COM)") (class "Default")
      (node (ref "C209") (pin "2") (pinfunction "2_2") (pintype "passive"))
      (node (ref "U202") (pin "5") (pinfunction "COM_5") (pintype "bidirectional"))
    )
    (net (code "88") (name "Net-(U202B-NO)") (class "Default")
      (node (ref "C213") (pin "2") (pinfunction "2_2") (pintype "passive"))
      (node (ref "C216") (pin "2") (pinfunction "2_2") (pintype "passive"))
      (node (ref "R226") (pin "1") (pinfunction "1_1") (pintype "passive"))
      (node (ref "U202") (pin "6") (pinfunction "NO_6") (pintype "bidirectional"))
      (node (ref "U203") (pin "6") (pinfunction "NO_6") (pintype "bidirectional"))
      (node (ref "U204") (pin "6") (pinfunction "NO_6") (pintype "bidirectional"))
      (node (ref "U205") (pin "6") (pinfunction "Y_6") (pintype "bidirectional"))
    )
    (net (code "89") (name "Net-(U205A-Y)") (class "Default")
      (node (ref "R211") (pin "1") (pinfunction "1_1") (pintype "passive"))
      (node (ref "U205") (pin "2") (pinfunction "Y_2") (pintype "bidirectional"))
      (node (ref "U205") (pin "3") (pinfunction "A_3") (pintype "bidirectional"))
    )
    (net (code "90") (name "Net-(U205B-Y)") (class "Default")
      (node (ref "R215") (pin "2") (pinfunction "2_2") (pintype "passive"))
      (node (ref "U205") (pin "4") (pinfunction "Y_4") (pintype "bidirectional"))
      (node (ref "U205") (pin "5") (pinfunction "A_5") (pintype "bidirectional"))
    )
    (net (code "91") (name "Net-(U205D-A)") (class "Default")
      (node (ref "R214") (pin "1") (pinfunction "1_1") (pintype "passive"))
      (node (ref "U205") (pin "10") (pinfunction "Y_10") (pintype "bidirectional"))
      (node (ref "U205") (pin "9") (pinfunction "A_9") (pintype "bidirectional"))
    )
    (net (code "92") (name "Net-(U205D-Y)") (class "Default")
      (node (ref "C212") (pin "2") (pinfunction "2_2") (pintype "passive"))
      (node (ref "C215") (pin "2") (pinfunction "2_2") (pintype "passive"))
      (node (ref "R223") (pin "1") (pinfunction "1_1") (pintype "passive"))
      (node (ref "U205") (pin "8") (pinfunction "Y_8") (pintype "bidirectional"))
    )
    (net (code "93") (name "Net-(U205E-A)") (class "Default")
      (node (ref "R210") (pin "2") (pinfunction "2_2") (pintype "passive"))
      (node (ref "U205") (pin "11") (pinfunction "A_11") (pintype "bidirectional"))
      (node (ref "U205") (pin "12") (pinfunction "Y_12") (pintype "bidirectional"))
    )
    (net (code "94") (name "Net-(U206-SENSE1)") (class "Default")
      (node (ref "R221") (pin "1") (pinfunction "1_1") (pintype "passive"))
      (node (ref "R222") (pin "1") (pinfunction "1_1") (pintype "passive"))
      (node (ref "U206") (pin "4") (pinfunction "SENSE1_4") (pintype "bidirectional"))
    )
    (net (code "95") (name "Net-(U206-SENSE2)") (class "Default")
      (node (ref "R216") (pin "1") (pinfunction "1_1") (pintype "passive"))
      (node (ref "R217") (pin "1") (pinfunction "1_1") (pintype "passive"))
      (node (ref "R218") (pin "1") (pinfunction "1_1") (pintype "passive"))
      (node (ref "R221") (pin "2") (pinfunction "2_2") (pintype "passive"))
      (node (ref "R222") (pin "2") (pinfunction "2_2") (pintype "passive"))
      (node (ref "U206") (pin "5") (pinfunction "SENSE2_5") (pintype "bidirectional"))
    )
    (net (code "96") (name "Net-(U207A-A)") (class "Default")
      (node (ref "R219") (pin "2") (pinfunction "2_2") (pintype "passive"))
      (node (ref "U207") (pin "1") (pinfunction "A_1") (pintype "bidirectional"))
      (node (ref "U207") (pin "5") (pinfunction "Y_5") (pintype "bidirectional"))
    )
    (net (code "97") (name "Net-(U207B-A)") (class "Default")
      (node (ref "C218") (pin "1") (pinfunction "1_1") (pintype "passive"))
      (node (ref "R219") (pin "1") (pinfunction "1_1") (pintype "passive"))
      (node (ref "R223") (pin "2") (pinfunction "2_2") (pintype "passive"))
      (node (ref "U207") (pin "3") (pinfunction "A_3") (pintype "bidirectional"))
    )
    (net (code "98") (name "Net-(U207C-A)") (class "Default")
      (node (ref "C219") (pin "1") (pinfunction "1_1") (pintype "passive"))
      (node (ref "R220") (pin "1") (pinfunction "1_1") (pintype "passive"))
      (node (ref "R226") (pin "2") (pinfunction "2_2") (pintype "passive"))
      (node (ref "U207") (pin "6") (pinfunction "A_6") (pintype "bidirectional"))
    )
    (net (code "99") (name "Net-(U207C-Y)") (class "Default")
      (node (ref "R212") (pin "1") (pinfunction "1_1") (pintype "passive"))
      (node (ref "R220") (pin "2") (pinfunction "2_2") (pintype "passive"))
      (node (ref "R225") (pin "1") (pinfunction "1_1") (pintype "passive"))
      (node (ref "U207") (pin "2") (pinfunction "Y_2") (pintype "bidirectional"))
    )
    (net (code "100") (name "Net-(U208A-A)") (class "Default")
      (node (ref "R225") (pin "2") (pinfunction "2_2") (pintype "passive"))
      (node (ref "U208") (pin "1") (pinfunction "A_1") (pintype "bidirectional"))
    )
    (net (code "101") (name "Net-(U208A-C)") (class "Default")
      (node (ref "R224") (pin "2") (pinfunction "2_2") (pintype "passive"))
      (node (ref "U208") (pin "6") (pinfunction "C_6") (pintype "bidirectional"))
    )
    (net (code "102") (name "Net-(U301-IN)") (class "Default")
      (node (ref "C308") (pin "2") (pinfunction "2_2") (pintype "passive"))
      (node (ref "U301") (pin "3") (pinfunction "IN_3") (pintype "bidirectional"))
    )
    (net (code "103") (name "Net-(U301-OUTN)") (class "Default")
      (node (ref "U301") (pin "4") (pinfunction "OUTN_4") (pintype "bidirectional"))
      (node (ref "U302") (pin "5") (pinfunction "MIX_IN_N_5") (pintype "bidirectional"))
    )
    (net (code "104") (name "Net-(U301-OUTP)") (class "Default")
      (node (ref "U301") (pin "5") (pinfunction "OUTP_5") (pintype "bidirectional"))
      (node (ref "U302") (pin "4") (pinfunction "MIX_IN_P_4") (pintype "bidirectional"))
    )
    (net (code "105") (name "Net-(U302-IBIAS)") (class "Default")
      (node (ref "R303") (pin "1") (pinfunction "1_1") (pintype "passive"))
      (node (ref "U302") (pin "1") (pinfunction "IBIAS_1") (pintype "bidirectional"))
    )
    (net (code "106") (name "Net-(U302-LDO2_OUT)") (class "Default")
      (node (ref "C304") (pin "2") (pinfunction "2_2") (pintype "passive"))
      (node (ref "U302") (pin "53") (pinfunction "LDO2_OUT_53") (pintype "bidirectional"))
    )
    (net (code "107") (name "Net-(U302-PIO4{slash}RXD1)") (class "Default")
      (node (ref "C318") (pin "2") (pinfunction "2_2") (pintype "passive"))
      (node (ref "R307") (pin "1") (pinfunction "1_1") (pintype "passive"))
      (node (ref "U302") (pin "24") (pinfunction "PIO4/RXD1_24") (pintype "bidirectional"))
    )
    (net (code "108") (name "Net-(U302-PIO5{slash}TXD1)") (class "Default")
      (node (ref "C317") (pin "2") (pinfunction "2_2") (pintype "passive"))
      (node (ref "R306") (pin "1") (pinfunction "1_1") (pintype "passive"))
      (node (ref "U302") (pin "21") (pinfunction "PIO5/TXD1_21") (pintype "bidirectional"))
    )
    (net (code "109") (name "Net-(U302-VDCTEST)") (class "Default")
      (node (ref "C307") (pin "1") (pinfunction "1_1") (pintype "passive"))
      (node (ref "U302") (pin "3") (pinfunction "VDCTEST_3") (pintype "bidirectional"))
    )
    (net (code "110") (name "Net-(U302-VDD_3V)") (class "Default")
      (node (ref "C301") (pin "1") (pinfunction "1_1") (pintype "passive"))
      (node (ref "C306") (pin "1") (pinfunction "1_1") (pintype "passive"))
      (node (ref "L301") (pin "2") (pinfunction "2_2") (pintype "passive"))
      (node (ref "L305") (pin "2") (pinfunction "2_2") (pintype "passive"))
      (node (ref "U302") (pin "50") (pinfunction "VDD_3V_50") (pintype "bidirectional"))
    )
    (net (code "111") (name "Net-(U302-VDD_B)") (class "Default")
      (node (ref "C313") (pin "2") (pinfunction "2_2") (pintype "passive"))
      (node (ref "U302") (pin "30") (pinfunction "VDD_B_30") (pintype "bidirectional"))
    )
    (net (code "112") (name "Net-(U302-VDD_C0)") (class "Default")
      (node (ref "C314") (pin "2") (pinfunction "2_2") (pintype "passive"))
      (node (ref "R305") (pin "2") (pinfunction "2_2") (pintype "passive"))
      (node (ref "U302") (pin "17") (pinfunction "VDD_C0_17") (pintype "bidirectional"))
    )
    (net (code "113") (name "Net-(U302-VDD_C1)") (class "Default")
      (node (ref "C312") (pin "2") (pinfunction "2_2") (pintype "passive"))
      (node (ref "U302") (pin "31") (pinfunction "VDD_C1_31") (pintype "bidirectional"))
    )
    (net (code "114") (name "Net-(U302-VDD_LNA)") (class "Default")
      (node (ref "C303") (pin "2") (pinfunction "2_2") (pintype "passive"))
      (node (ref "U302") (pin "55") (pinfunction "VDD_LNA_55") (pintype "bidirectional"))
    )
    (net (code "115") (name "Net-(U302-VDD_PLL)") (class "Default")
      (node (ref "C311") (pin "1") (pinfunction "1_1") (pintype "passive"))
      (node (ref "R305") (pin "1") (pinfunction "1_1") (pintype "passive"))
      (node (ref "U302") (pin "9") (pinfunction "VDD_PLL_9") (pintype "bidirectional"))
    )
    (net (code "116") (name "Net-(U302-VDD_RF)") (class "Default")
      (node (ref "C305") (pin "2") (pinfunction "2_2") (pintype "passive"))
      (node (ref "U302") (pin "51") (pinfunction "VDD_RF_51") (pintype "bidirectional"))
    )
    (net (code "117") (name "Net-(U302-VSS_PLL)") (class "Default")
      (node (ref "C311") (pin "2") (pinfunction "2_2") (pintype "passive"))
      (node (ref "U302") (pin "8") (pinfunction "VSS_PLL_8") (pintype "bidirectional"))
    )
    (net (code "118") (name "Net-(U303-IN)") (class "Default")
      (node (ref "L304") (pin "2") (pinfunction "2_2") (pintype "passive"))
      (node (ref "R304") (pin "1") (pinfunction "1_1") (pintype "passive"))
      (node (ref "U303") (pin "4") (pinfunction "IN_4") (pintype "bidirectional"))
    )
    (net (code "119") (name "Net-(U303-OUT)") (class "Default")
      (node (ref "L302") (pin "1") (pinfunction "1_1") (pintype "passive"))
      (node (ref "U303") (pin "5") (pinfunction "OUT_5") (pintype "bidirectional"))
    )
    (net (code "120") (name "Net-(U304-IN)") (class "Default")
      (node (ref "L302") (pin "2") (pinfunction "2_2") (pintype "passive"))
      (node (ref "U304") (pin "6") (pinfunction "IN_6") (pintype "bidirectional"))
    )
    (net (code "121") (name "Net-(U304-OUT)") (class "Default")
      (node (ref "L303") (pin "1") (pinfunction "1_1") (pintype "passive"))
      (node (ref "U304") (pin "3") (pinfunction "OUT_3") (pintype "bidirectional"))
    )
    (net (code "122") (name "Net-(U401-GPIO_1)") (class "Default")
      (node (ref "R406") (pin "1") (pinfunction "1_1") (pintype "passive"))
      (node (ref "U401") (pin "8") (pinfunction "GPIO_1_8") (pintype "bidirectional"))
    )
    (net (code "123") (name "Net-(U401-GPIO_2)") (class "Default")
      (node (ref "R403") (pin "1") (pinfunction "1_1") (pintype "passive"))
      (node (ref "U401") (pin "9") (pinfunction "GPIO_2_9") (pintype "bidirectional"))
    )
    (net (code "124") (name "Net-(U401-TX)") (class "Default")
      (node (ref "C404") (pin "2") (pinfunction "2_2") (pintype "passive"))
      (node (ref "L408") (pin "2") (pinfunction "2_2") (pintype "passive"))
      (node (ref "U401") (pin "2") (pinfunction "TX_2") (pintype "bidirectional"))
    )
    (net (code "125") (name "Net-(U401-VDD_DIG)") (class "Default")
      (node (ref "C410") (pin "1") (pinfunction "1_1") (pintype "passive"))
      (node (ref "C411") (pin "1") (pinfunction "1_1") (pintype "passive"))
      (node (ref "L410") (pin "1") (pinfunction "1_1") (pintype "passive"))
      (node (ref "U401") (pin "12") (pinfunction "VDD_DIG_12") (pintype "bidirectional"))
    )
    (net (code "126") (name "Net-(U401-VDD_RF)") (class "Default")
      (node (ref "C414") (pin "1") (pinfunction "1_1") (pintype "passive"))
      (node (ref "C415") (pin "1") (pinfunction "1_1") (pintype "passive"))
      (node (ref "C416") (pin "1") (pinfunction "1_1") (pintype "passive"))
      (node (ref "C417") (pin "1") (pinfunction "1_1") (pintype "passive"))
      (node (ref "L409") (pin "2") (pinfunction "2_2") (pintype "passive"))
      (node (ref "R405") (pin "2") (pinfunction "2_2") (pintype "passive"))
      (node (ref "U401") (pin "1") (pinfunction "VDD_RF_1") (pintype "bidirectional"))
    )
    (net (code "127") (name "Net-(U401-VDR)") (class "Default")
      (node (ref "C420") (pin "1") (pinfunction "1_1") (pintype "passive"))
      (node (ref "C421") (pin "1") (pinfunction "1_1") (pintype "passive"))
      (node (ref "U401") (pin "10") (pinfunction "VDR_10") (pintype "bidirectional"))
    )
    (net (code "128") (name "Net-(U401-XOUT)") (class "Default")
      (node (ref "C401") (pin "1") (pinfunction "1_1") (pintype "passive"))
      (node (ref "U401") (pin "18") (pinfunction "XOUT_18") (pintype "bidirectional"))
    )
    (net (code "129") (name "Net-(U501-NC)") (class "Default")
      (node (ref "C506") (pin "1") (pinfunction "1_1") (pintype "passive"))
      (node (ref "U501") (pin "4") (pinfunction "NC_4") (pintype "bidirectional"))
    )
    (net (code "130") (name "Net-(U502-FB)") (class "Default")
      (node (ref "R503") (pin "1") (pinfunction "1_1") (pintype "passive"))
      (node (ref "R504") (pin "2") (pinfunction "2_2") (pintype "passive"))
      (node (ref "U502") (pin "10") (pinfunction "FB_10") (pintype "bidirectional"))
    )
    (net (code "131") (name "Net-(U502-L)") (class "Default")
      (node (ref "L501") (pin "2") (pinfunction "2_2") (pintype "passive"))
      (node (ref "U502") (pin "3") (pinfunction "L_3") (pintype "bidirectional"))
    )
    (net (code "132") (name "Net-(U502-VAUX)") (class "Default")
      (node (ref "C510") (pin "1") (pinfunction "1_1") (pintype "passive"))
      (node (ref "U502") (pin "1") (pinfunction "VAUX_1") (pintype "bidirectional"))
    )
    (net (code "133") (name "Net-(U503-NC)") (class "Default")
      (node (ref "C516") (pin "1") (pinfunction "1_1") (pintype "passive"))
      (node (ref "U503") (pin "4") (pinfunction "NC_4") (pintype "bidirectional"))
    )
    (net (code "134") (name "Net-(U504-NC)") (class "Default")
      (node (ref "C526") (pin "1") (pinfunction "1_1") (pintype "passive"))
      (node (ref "U504") (pin "4") (pinfunction "NC_4") (pintype "bidirectional"))
    )
    (net (code "135") (name "PULLUP_HYG") (class "Default")
      (node (ref "C113") (pin "1") (pinfunction "1_1") (pintype "passive"))
      (node (ref "Q202") (pin "1") (pinfunction "G_1") (pintype "passive"))
      (node (ref "R104") (pin "1") (pinfunction "1_1") (pintype "passive"))
    )
    (net (code "136") (name "PULLUP_TMP") (class "Default")
      (node (ref "C124") (pin "2") (pinfunction "2_2") (pintype "passive"))
      (node (ref "Q201") (pin "1") (pinfunction "G_1") (pintype "passive"))
      (node (ref "R118") (pin "1") (pinfunction "1_1") (pintype "passive"))
    )
    (net (code "137") (name "RADIO_ANT_PRI") (class "Default")
      (node (ref "C405") (pin "1") (pinfunction "1_1") (pintype "passive"))
      (node (ref "C409") (pin "2") (pinfunction "2_2") (pintype "passive"))
      (node (ref "L402") (pin "1") (pinfunction "1_1") (pintype "passive"))
      (node (ref "L406") (pin "2") (pinfunction "2_2") (pintype "passive"))
    )
    (net (code "138") (name "RADIO_CLK") (class "Default")
      (node (ref "C401") (pin "2") (pinfunction "2_2") (pintype "passive"))
      (node (ref "R309") (pin "1") (pinfunction "1_1") (pintype "passive"))
    )
    (net (code "139") (name "RADIO_PROBE_POINT") (class "Default")
      (node (ref "R403") (pin "2") (pinfunction "2_2") (pintype "passive"))
      (node (ref "TP1") (pin "TP") (pinfunction "TP_TP") (pintype "input"))
    )
    (net (code "140") (name "REF_R_THERM") (class "Default")
      (node (ref "C116") (pin "2") (pinfunction "2_2") (pintype "passive"))
      (node (ref "R103") (pin "1") (pinfunction "1_1") (pintype "passive"))
      (node (ref "R125") (pin "1") (pinfunction "1_1") (pintype "passive"))
      (node (ref "R209") (pin "1") (pinfunction "1_1") (pintype "passive"))
    )
    (net (code "141") (name "RPM_CLOCK") (class "Default")
      (node (ref "R112") (pin "1") (pinfunction "1_1") (pintype "passive"))
    )
    (net (code "142") (name "SHUTDOWN") (class "Default")
      (node (ref "C522") (pin "1") (pinfunction "1_1") (pintype "passive"))
      (node (ref "Q503") (pin "2") (pinfunction "G_2") (pintype "passive"))
      (node (ref "R117") (pin "1") (pinfunction "1_1") (pintype "passive"))
      (node (ref "R511") (pin "1") (pinfunction "1_1") (pintype "passive"))
    )
    (net (code "143") (name "SPDT1") (class "Default")
      (node (ref "C117") (pin "2") (pinfunction "2_2") (pintype "passive"))
      (node (ref "R105") (pin "1") (pinfunction "1_1") (pintype "passive"))
      (node (ref "U202") (pin "1") (pinfunction "IN_1") (pintype "bidirectional"))
    )
    (net (code "144") (name "SPDT2") (class "Default")
      (node (ref "C118") (pin "2") (pinfunction "2_2") (pintype "passive"))
      (node (ref "R107") (pin "1") (pinfunction "1_1") (pintype "passive"))
      (node (ref "U203") (pin "1") (pinfunction "IN_1") (pintype "bidirectional"))
    )
    (net (code "145") (name "SPDT3") (class "Default")
      (node (ref "C119") (pin "2") (pinfunction "2_2") (pintype "passive"))
      (node (ref "R108") (pin "1") (pinfunction "1_1") (pintype "passive"))
      (node (ref "U204") (pin "1") (pinfunction "IN_1") (pintype "bidirectional"))
    )
    (net (code "146") (name "SPI_CS") (class "Default")
      (node (ref "J601") (pin "10") (pinfunction "12_10") (pintype "passive"))
      (node (ref "U101") (pin "20") (pinfunction "PB2_20") (pintype "bidirectional"))
      (node (ref "U601") (pin "1") (pinfunction "~{CS}_1") (pintype "input"))
    )
    (net (code "147") (name "SPI_SCK") (class "Default")
      (node (ref "J601") (pin "4") (pinfunction "15_4") (pintype "passive"))
      (node (ref "R120") (pin "1") (pinfunction "1_1") (pintype "passive"))
      (node (ref "U601") (pin "6") (pinfunction "SCK_6") (pintype "input"))
    )
    (net (code "148") (name "SPI_SCK_RADIO") (class "Default")
      (node (ref "R122") (pin "1") (pinfunction "1_1") (pintype "passive"))
      (node (ref "U401") (pin "15") (pinfunction "SCLK_15") (pintype "bidirectional"))
    )
    (net (code "149") (name "SPI_SDI") (class "Default")
      (node (ref "J601") (pin "6") (pinfunction "14_6") (pintype "passive"))
      (node (ref "U101") (pin "27") (pinfunction "PB14_27") (pintype "bidirectional"))
      (node (ref "U401") (pin "13") (pinfunction "SDO_13") (pintype "bidirectional"))
      (node (ref "U601") (pin "2") (pinfunction "SO_2") (pintype "bidirectional"))
    )
    (net (code "150") (name "SPI_SDO") (class "Default")
      (node (ref "J601") (pin "8") (pinfunction "13_8") (pintype "passive"))
      (node (ref "U101") (pin "28") (pinfunction "PB15_28") (pintype "bidirectional"))
      (node (ref "U401") (pin "14") (pinfunction "SDI_14") (pintype "bidirectional"))
      (node (ref "U601") (pin "5") (pinfunction "SI_5") (pintype "input"))
    )
    (net (code "151") (name "SPST1") (class "Default")
      (node (ref "C120") (pin "2") (pinfunction "2_2") (pintype "passive"))
      (node (ref "R109") (pin "1") (pinfunction "1_1") (pintype "passive"))
      (node (ref "U201") (pin "13") (pinfunction "IN_13") (pintype "bidirectional"))
    )
    (net (code "152") (name "SPST2") (class "Default")
      (node (ref "U101") (pin "13") (pinfunction "PA3_13") (pintype "bidirectional"))
      (node (ref "U201") (pin "5") (pinfunction "IN_5") (pintype "bidirectional"))
    )
    (net (code "153") (name "SPST3") (class "Default")
      (node (ref "U101") (pin "3") (pinfunction "PC14_3") (pintype "bidirectional"))
      (node (ref "U201") (pin "6") (pinfunction "IN_6") (pintype "bidirectional"))
    )
    (net (code "154") (name "SPST4") (class "Default")
      (node (ref "U101") (pin "4") (pinfunction "PC15_4") (pintype "bidirectional"))
      (node (ref "U201") (pin "12") (pinfunction "IN_12") (pintype "bidirectional"))
    )
    (net (code "155") (name "SW") (class "Default")
      (node (ref "C524") (pin "1") (pinfunction "1_1") (pintype "passive"))
      (node (ref "R509") (pin "1") (pinfunction "1_1") (pintype "passive"))
      (node (ref "R513") (pin "2") (pinfunction "2_2") (pintype "passive"))
      (node (ref "U101") (pin "16") (pinfunction "PA6_16") (pintype "bidirectional"))
    )
    (net (code "156") (name "VBAT") (class "Default")
      (node (ref "C504") (pin "2") (pinfunction "2_2") (pintype "passive"))
      (node (ref "C505") (pin "2") (pinfunction "2_2") (pintype "passive"))
      (node (ref "C511") (pin "1") (pinfunction "1_1") (pintype "passive"))
      (node (ref "D501") (pin "C") (pinfunction "C_C") (pintype "passive"))
      (node (ref "F501") (pin "2") (pinfunction "2_2") (pintype "passive"))
      (node (ref "J602") (pin "6") (pinfunction "8_6") (pintype "passive"))
      (node (ref "Q501") (pin "2") (pinfunction "S_2") (pintype "passive"))
      (node (ref "R501") (pin "1") (pinfunction "1_1") (pintype "passive"))
      (node (ref "S501") (pin "1") (pinfunction "1_1") (pintype "passive"))
    )
    (net (code "157") (name "VBAT_MON") (class "Default")
      (node (ref "C523") (pin "1") (pinfunction "1_1") (pintype "passive"))
      (node (ref "R508") (pin "1") (pinfunction "1_1") (pintype "passive"))
      (node (ref "R512") (pin "2") (pinfunction "2_2") (pintype "passive"))
      (node (ref "U101") (pin "15") (pinfunction "PA5_15") (pintype "bidirectional"))
    )
    (net (code "158") (name "VBAT_SW") (class "Default")
      (node (ref "C512") (pin "1") (pinfunction "1_1") (pintype "passive"))
      (node (ref "L501") (pin "1") (pinfunction "1_1") (pintype "passive"))
      (node (ref "Q501") (pin "3") (pinfunction "D_3") (pintype "passive"))
      (node (ref "R505") (pin "2") (pinfunction "2_2") (pintype "passive"))
      (node (ref "R508") (pin "2") (pinfunction "2_2") (pintype "passive"))
      (node (ref "U502") (pin "5") (pinfunction "VIN_5") (pintype "bidirectional"))
      (node (ref "U502") (pin "6") (pinfunction "EN_6") (pintype "bidirectional"))
      (node (ref "U502") (pin "7") (pinfunction "UVLO_7") (pintype "bidirectional"))
      (node (ref "U502") (pin "8") (pinfunction "PS_8") (pintype "bidirectional"))
    )
    (net (code "159") (name "V_BOOST") (class "Default")
      (node (ref "C214") (pin "1") (pinfunction "1_1") (pintype "passive"))
      (node (ref "C501") (pin "1") (pinfunction "1_1") (pintype "passive"))
      (node (ref "C507") (pin "1") (pinfunction "1_1") (pintype "passive"))
      (node (ref "C508") (pin "1") (pinfunction "1_1") (pintype "passive"))
      (node (ref "C509") (pin "1") (pinfunction "1_1") (pintype "passive"))
      (node (ref "C513") (pin "1") (pinfunction "1_1") (pintype "passive"))
      (node (ref "C520") (pin "1") (pinfunction "1_1") (pintype "passive"))
      (node (ref "J201") (pin "9") (pinfunction "2_9") (pintype "passive"))
      (node (ref "J601") (pin "15") (pinfunction "8_15") (pintype "passive"))
      (node (ref "J602") (pin "5") (pinfunction "3_5") (pintype "passive"))
      (node (ref "R503") (pin "2") (pinfunction "2_2") (pintype "passive"))
      (node (ref "U501") (pin "1") (pinfunction "IN_1") (pintype "bidirectional"))
      (node (ref "U501") (pin "3") (pinfunction "EN_3") (pintype "bidirectional"))
      (node (ref "U502") (pin "2") (pinfunction "VOUT_2") (pintype "bidirectional"))
      (node (ref "U503") (pin "1") (pinfunction "IN_1") (pintype "bidirectional"))
      (node (ref "U503") (pin "3") (pinfunction "EN_3") (pintype "bidirectional"))
      (node (ref "U504") (pin "1") (pinfunction "IN_1") (pintype "bidirectional"))
      (node (ref "U504") (pin "3") (pinfunction "EN_3") (pintype "bidirectional"))
    )
    (net (code "160") (name "XDATA_RX") (class "Default")
      (node (ref "C606") (pin "2") (pinfunction "2_2") (pintype "passive"))
      (node (ref "J602") (pin "2") (pinfunction "10_2") (pintype "passive"))
      (node (ref "R116") (pin "1") (pinfunction "1_1") (pintype "passive"))
    )
    (net (code "161") (name "XDATA_SWCLK") (class "Default")
      (node (ref "D605") (pin "C") (pinfunction "C_C") (pintype "passive"))
      (node (ref "J602") (pin "8") (pinfunction "7_8") (pintype "passive"))
      (node (ref "R121") (pin "1") (pinfunction "1_1") (pintype "passive"))
    )
    (net (code "162") (name "XDATA_SWDIO") (class "Default")
      (node (ref "D606") (pin "C") (pinfunction "C_C") (pintype "passive"))
      (node (ref "J602") (pin "9") (pinfunction "5_9") (pintype "passive"))
      (node (ref "R119") (pin "1") (pinfunction "1_1") (pintype "passive"))
    )
    (net (code "163") (name "XDATA_TX") (class "Default")
      (node (ref "C607") (pin "2") (pinfunction "2_2") (pintype "passive"))
      (node (ref "J602") (pin "3") (pinfunction "2_3") (pintype "passive"))
      (node (ref "R115") (pin "1") (pinfunction "1_1") (pintype "passive"))
    )
    (net (code "164") (name "unconnected-(G501-+-Pad+@1)") (class "Default")
      (node (ref "G501") (pin "+@1") (pinfunction "+_+@1") (pintype "passive"))
    )
    (net (code "165") (name "unconnected-(J601-2-Pad3)") (class "Default")
      (node (ref "J601") (pin "3") (pinfunction "2_3") (pintype "passive"))
    )
    (net (code "166") (name "unconnected-(J601-3-Pad5)") (class "Default")
      (node (ref "J601") (pin "5") (pinfunction "3_5") (pintype "passive"))
    )
    (net (code "167") (name "unconnected-(J601-4-Pad7)") (class "Default")
      (node (ref "J601") (pin "7") (pinfunction "4_7") (pintype "passive"))
    )
    (net (code "168") (name "unconnected-(J601-5-Pad9)") (class "Default")
      (node (ref "J601") (pin "9") (pinfunction "5_9") (pintype "passive"))
    )
    (net (code "169") (name "unconnected-(J601-6-Pad11)") (class "Default")
      (node (ref "J601") (pin "11") (pinfunction "6_11") (pintype "passive"))
    )
    (net (code "170") (name "unconnected-(J601-7-Pad13)") (class "Default")
      (node (ref "J601") (pin "13") (pinfunction "7_13") (pintype "passive"))
    )
    (net (code "171") (name "unconnected-(U101C-BOOT0-Pad44)") (class "Default")
      (node (ref "U101") (pin "44") (pinfunction "BOOT0_44") (pintype "bidirectional"))
    )
    (net (code "172") (name "unconnected-(U204B-COM-Pad5)") (class "Default")
      (node (ref "U204") (pin "5") (pinfunction "COM_5") (pintype "bidirectional"))
    )
    (net (code "173") (name "unconnected-(U208B-GND-Pad2)") (class "Default")
      (node (ref "U208") (pin "2") (pinfunction "GND_2") (pintype "bidirectional"))
    )
    (net (code "174") (name "unconnected-(U208B-VCC-Pad5)") (class "Default")
      (node (ref "U208") (pin "5") (pinfunction "VCC_5") (pintype "bidirectional"))
    )
    (net (code "175") (name "unconnected-(U302-CFG_PIN{slash}TMS-Pad43)") (class "Default")
      (node (ref "U302") (pin "43") (pinfunction "CFG_PIN/TMS_43") (pintype "bidirectional"))
    )
    (net (code "176") (name "unconnected-(U302-DCDC_EN-Pad26)") (class "Default")
      (node (ref "U302") (pin "26") (pinfunction "DCDC_EN_26") (pintype "bidirectional"))
    )
    (net (code "177") (name "unconnected-(U302-EP-Pad57)") (class "Default")
      (node (ref "U302") (pin "57") (pinfunction "EP_57") (pintype "bidirectional"))
    )
    (net (code "178") (name "unconnected-(U302-LNAIN-Pad56)") (class "Default")
      (node (ref "U302") (pin "56") (pinfunction "LNAIN_56") (pintype "bidirectional"))
    )
    (net (code "179") (name "unconnected-(U302-LNAOUT-Pad2)") (class "Default")
      (node (ref "U302") (pin "2") (pinfunction "LNAOUT_2") (pintype "bidirectional"))
    )
    (net (code "180") (name "unconnected-(U302-NC1-Pad27)") (class "Default")
      (node (ref "U302") (pin "27") (pinfunction "NC1_27") (pintype "bidirectional"))
    )
    (net (code "181") (name "unconnected-(U302-NC2-Pad46)") (class "Default")
      (node (ref "U302") (pin "46") (pinfunction "NC2_46") (pintype "bidirectional"))
    )
    (net (code "182") (name "unconnected-(U302-PIO2-Pad33)") (class "Default")
      (node (ref "U302") (pin "33") (pinfunction "PIO2_33") (pintype "bidirectional"))
    )
    (net (code "183") (name "unconnected-(U302-PIO3-Pad34)") (class "Default")
      (node (ref "U302") (pin "34") (pinfunction "PIO3_34") (pintype "bidirectional"))
    )
    (net (code "184") (name "unconnected-(U302-PIO6-Pad20)") (class "Default")
      (node (ref "U302") (pin "20") (pinfunction "PIO6_20") (pintype "bidirectional"))
    )
    (net (code "185") (name "unconnected-(U302-PIO7{slash}EXTINT0-Pad44)") (class "Default")
      (node (ref "U302") (pin "44") (pinfunction "PIO7/EXTINT0_44") (pintype "bidirectional"))
    )
    (net (code "186") (name "unconnected-(U302-PIO8{slash}EXTINT1-Pad45)") (class "Default")
      (node (ref "U302") (pin "45") (pinfunction "PIO8/EXTINT1_45") (pintype "bidirectional"))
    )
    (net (code "187") (name "unconnected-(U302-PIO13{slash}CFG_CLK0-Pad41)") (class "Default")
      (node (ref "U302") (pin "41") (pinfunction "PIO13/CFG_CLK0_41") (pintype "bidirectional"))
    )
    (net (code "188") (name "unconnected-(U302-PIO14{slash}CFG_CLK1-Pad35)") (class "Default")
      (node (ref "U302") (pin "35") (pinfunction "PIO14/CFG_CLK1_35") (pintype "bidirectional"))
    )
    (net (code "189") (name "unconnected-(U302-PIO15{slash}CFG_CLK2-Pad36)") (class "Default")
      (node (ref "U302") (pin "36") (pinfunction "PIO15/CFG_CLK2_36") (pintype "bidirectional"))
    )
    (net (code "190") (name "unconnected-(U302-PIO17{slash}CFG_FFU2-Pad37)") (class "Default")
      (node (ref "U302") (pin "37") (pinfunction "PIO17/CFG_FFU2_37") (pintype "bidirectional"))
    )
    (net (code "191") (name "unconnected-(U302-PIO18{slash}CFG_FFU3-Pad16)") (class "Default")
      (node (ref "U302") (pin "16") (pinfunction "PIO18/CFG_FFU3_16") (pintype "bidirectional"))
    )
    (net (code "192") (name "unconnected-(U302-PIO19{slash}CFG_COM0-Pad32)") (class "Default")
      (node (ref "U302") (pin "32") (pinfunction "PIO19/CFG_COM0_32") (pintype "bidirectional"))
    )
    (net (code "193") (name "unconnected-(U302-PIO20{slash}CFG_COM1-Pad18)") (class "Default")
      (node (ref "U302") (pin "18") (pinfunction "PIO20/CFG_COM1_18") (pintype "bidirectional"))
    )
    (net (code "194") (name "unconnected-(U302-PIO21{slash}CFG_GPS0-Pad19)") (class "Default")
      (node (ref "U302") (pin "19") (pinfunction "PIO21/CFG_GPS0_19") (pintype "bidirectional"))
    )
    (net (code "195") (name "unconnected-(U302-PIO22{slash}CFG_GPS1-Pad11)") (class "Default")
      (node (ref "U302") (pin "11") (pinfunction "PIO22/CFG_GPS1_11") (pintype "bidirectional"))
    )
    (net (code "196") (name "unconnected-(U302-PIO23{slash}CFG_GPS2-Pad10)") (class "Default")
      (node (ref "U302") (pin "10") (pinfunction "PIO23/CFG_GPS2_10") (pintype "bidirectional"))
    )
    (net (code "197") (name "unconnected-(U302-RTC_XTAL_I-Pad7)") (class "Default")
      (node (ref "U302") (pin "7") (pinfunction "RTC_XTAL_I_7") (pintype "bidirectional"))
    )
    (net (code "198") (name "unconnected-(U302-RTC_XTAL_O-Pad6)") (class "Default")
      (node (ref "U302") (pin "6") (pinfunction "RTC_XTAL_O_6") (pintype "bidirectional"))
    )
    (net (code "199") (name "unconnected-(U302-SAFEBOOT_N{slash}TDI-Pad38)") (class "Default")
      (node (ref "U302") (pin "38") (pinfunction "SAFEBOOT_N/TDI_38") (pintype "bidirectional"))
    )
    (net (code "200") (name "unconnected-(U302-TCK-Pad40)") (class "Default")
      (node (ref "U302") (pin "40") (pinfunction "TCK_40") (pintype "bidirectional"))
    )
    (net (code "201") (name "unconnected-(U302-TCXO_POWER-Pad47)") (class "Default")
      (node (ref "U302") (pin "47") (pinfunction "TCXO_POWER_47") (pintype "bidirectional"))
    )
    (net (code "202") (name "unconnected-(U302-TDO-Pad39)") (class "Default")
      (node (ref "U302") (pin "39") (pinfunction "TDO_39") (pintype "bidirectional"))
    )
    (net (code "203") (name "unconnected-(U302-USB_DM-Pad14)") (class "Default")
      (node (ref "U302") (pin "14") (pinfunction "USB_DM_14") (pintype "bidirectional"))
    )
    (net (code "204") (name "unconnected-(U302-USB_DP-Pad13)") (class "Default")
      (node (ref "U302") (pin "13") (pinfunction "USB_DP_13") (pintype "bidirectional"))
    )
    (net (code "205") (name "unconnected-(U302-VDD_ANA-Pad54)") (class "Default")
      (node (ref "U302") (pin "54") (pinfunction "VDD_ANA_54") (pintype "bidirectional"))
    )
    (net (code "206") (name "unconnected-(U302-VDD_SYNTH-Pad52)") (class "Default")
      (node (ref "U302") (pin "52") (pinfunction "VDD_SYNTH_52") (pintype "bidirectional"))
    )
    (net (code "207") (name "unconnected-(U302-V_BCKP-Pad28)") (class "Default")
      (node (ref "U302") (pin "28") (pinfunction "V_BCKP_28") (pintype "bidirectional"))
    )
    (net (code "208") (name "unconnected-(U302-V_TH-Pad22)") (class "Default")
      (node (ref "U302") (pin "22") (pinfunction "V_TH_22") (pintype "bidirectional"))
    )
    (net (code "209") (name "unconnected-(U302-XTAL_O-Pad48)") (class "Default")
      (node (ref "U302") (pin "48") (pinfunction "XTAL_O_48") (pintype "bidirectional"))
    )
    (net (code "210") (name "unconnected-(U401-GPIO_0-Pad7)") (class "Default")
      (node (ref "U401") (pin "7") (pinfunction "GPIO_0_7") (pintype "bidirectional"))
    )
    (net (code "211") (name "unconnected-(U401-NC1-Pad3)") (class "Default")
      (node (ref "U401") (pin "3") (pinfunction "NC1_3") (pintype "bidirectional"))
    )
    (net (code "212") (name "unconnected-(U401-NC2-Pad4)") (class "Default")
      (node (ref "U401") (pin "4") (pinfunction "NC2_4") (pintype "bidirectional"))
    )
    (net (code "213") (name "unconnected-(U401-NC3-Pad5)") (class "Default")
      (node (ref "U401") (pin "5") (pinfunction "NC3_5") (pintype "bidirectional"))
    )
    (net (code "214") (name "unconnected-(U401-NC4-Pad6)") (class "Default")
      (node (ref "U401") (pin "6") (pinfunction "NC4_6") (pintype "bidirectional"))
    )
    (net (code "215") (name "unconnected-(U401-NC5-Pad11)") (class "Default")
      (node (ref "U401") (pin "11") (pinfunction "NC5_11") (pintype "bidirectional"))
    )
    (net (code "216") (name "unconnected-(U401-NIRQ-Pad17)") (class "Default")
      (node (ref "U401") (pin "17") (pinfunction "NIRQ_17") (pintype "bidirectional"))
    )
    (net (code "217") (name "unconnected-(U401-XIN-Pad19)") (class "Default")
      (node (ref "U401") (pin "19") (pinfunction "XIN_19") (pintype "bidirectional"))
    )
  )
)
